# 01-MCU_Core.net
KiCad netlist of a schematic drawn in Altium Designer
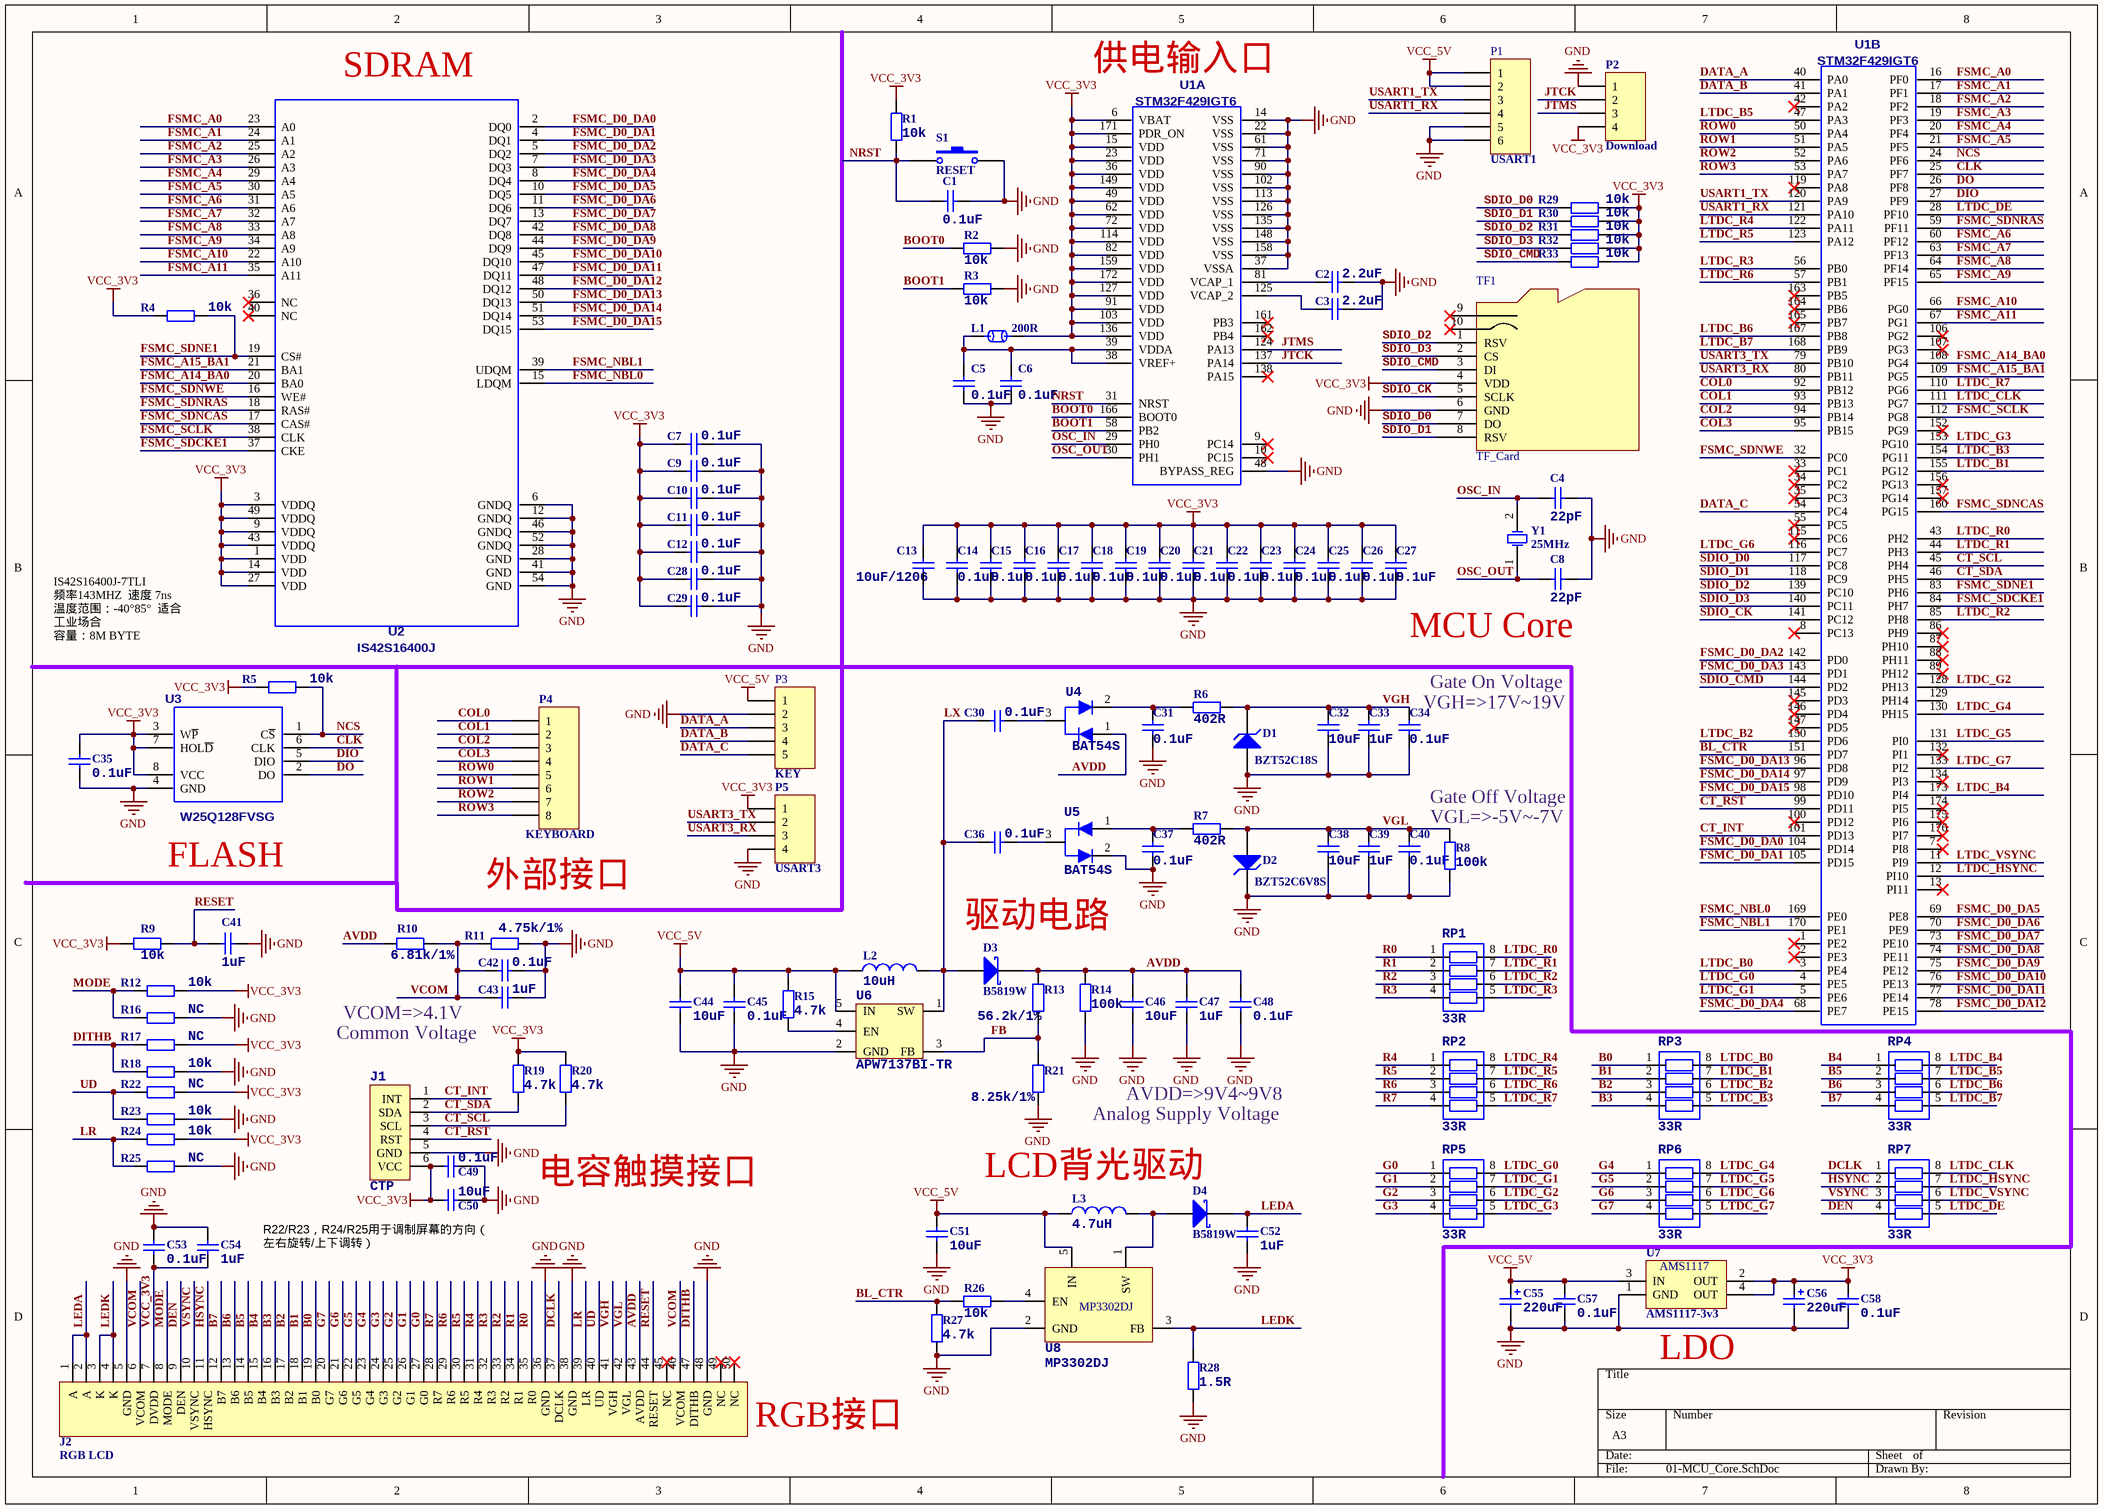
[diagram p0: 01-MCU_Core.SchDoc]

(export (version "E")
  (design (tool "Eeschema 10.0.6"))
  (components
    (comp (ref "C1")
      (value "0.1uF")
      (footprint "C0603")
      (description "CAP CER 10000PF 100V X7R 0603")
      (fields
        (field (name "MANUFACTURER") "TDK Corporation")
        (field (name "MANUFACTURER PART NUMBER") "C1608X7R2A103K080AA")
      )
      (libsource (lib "Desiger_Schlib") (part "Cap1"))
    )
    (comp (ref "C2")
      (value "2.2uF")
      (footprint "C0603")
      (description "CAP CER 10000PF 100V X7R 0603")
      (fields
        (field (name "MANUFACTURER") "TDK Corporation")
        (field (name "MANUFACTURER PART NUMBER") "C1608X7R2A103K080AA")
      )
      (libsource (lib "Desiger_Schlib") (part "Cap1"))
    )
    (comp (ref "C3")
      (value "2.2uF")
      (footprint "C0603")
      (description "CAP CER 10000PF 100V X7R 0603")
      (fields
        (field (name "MANUFACTURER") "TDK Corporation")
        (field (name "MANUFACTURER PART NUMBER") "C1608X7R2A103K080AA")
      )
      (libsource (lib "Desiger_Schlib") (part "Cap1"))
    )
    (comp (ref "C4")
      (value "22pF")
      (footprint "C0603")
      (description "CAP CER 10000PF 100V X7R 0603")
      (fields
        (field (name "MANUFACTURER") "TDK Corporation")
        (field (name "MANUFACTURER PART NUMBER") "C1608X7R2A103K080AA")
      )
      (libsource (lib "Desiger_Schlib") (part "Cap1"))
    )
    (comp (ref "C5")
      (value "0.1uF")
      (footprint "C0603")
      (description "CAP CER 10000PF 100V X7R 0603")
      (fields
        (field (name "MANUFACTURER") "TDK Corporation")
        (field (name "MANUFACTURER PART NUMBER") "C1608X7R2A103K080AA")
      )
      (libsource (lib "Desiger_Schlib") (part "Cap1"))
    )
    (comp (ref "C6")
      (value "0.1uF")
      (footprint "C0603")
      (description "CAP CER 10000PF 100V X7R 0603")
      (fields
        (field (name "MANUFACTURER") "TDK Corporation")
        (field (name "MANUFACTURER PART NUMBER") "C1608X7R2A103K080AA")
      )
      (libsource (lib "Desiger_Schlib") (part "Cap1"))
    )
    (comp (ref "C7")
      (value "0.1uF")
      (footprint "C0603")
      (description "CAP CER 10000PF 100V X7R 0603")
      (fields
        (field (name "MANUFACTURER") "TDK Corporation")
        (field (name "MANUFACTURER PART NUMBER") "C1608X7R2A103K080AA")
      )
      (libsource (lib "Desiger_Schlib") (part "Cap1"))
    )
    (comp (ref "C8")
      (value "22pF")
      (footprint "C0603")
      (description "CAP CER 10000PF 100V X7R 0603")
      (fields
        (field (name "MANUFACTURER") "TDK Corporation")
        (field (name "MANUFACTURER PART NUMBER") "C1608X7R2A103K080AA")
      )
      (libsource (lib "Desiger_Schlib") (part "Cap1"))
    )
    (comp (ref "C9")
      (value "0.1uF")
      (footprint "C0603")
      (description "CAP CER 10000PF 100V X7R 0603")
      (fields
        (field (name "MANUFACTURER") "TDK Corporation")
        (field (name "MANUFACTURER PART NUMBER") "C1608X7R2A103K080AA")
      )
      (libsource (lib "Desiger_Schlib") (part "Cap1"))
    )
    (comp (ref "C10")
      (value "0.1uF")
      (footprint "C0603")
      (description "CAP CER 10000PF 100V X7R 0603")
      (fields
        (field (name "MANUFACTURER") "TDK Corporation")
        (field (name "MANUFACTURER PART NUMBER") "C1608X7R2A103K080AA")
      )
      (libsource (lib "Desiger_Schlib") (part "Cap1"))
    )
    (comp (ref "C11")
      (value "0.1uF")
      (footprint "C0603")
      (description "CAP CER 10000PF 100V X7R 0603")
      (fields
        (field (name "MANUFACTURER") "TDK Corporation")
        (field (name "MANUFACTURER PART NUMBER") "C1608X7R2A103K080AA")
      )
      (libsource (lib "Desiger_Schlib") (part "Cap1"))
    )
    (comp (ref "C12")
      (value "0.1uF")
      (footprint "C0603")
      (description "CAP CER 10000PF 100V X7R 0603")
      (fields
        (field (name "MANUFACTURER") "TDK Corporation")
        (field (name "MANUFACTURER PART NUMBER") "C1608X7R2A103K080AA")
      )
      (libsource (lib "Desiger_Schlib") (part "Cap1"))
    )
    (comp (ref "C13")
      (value "10uF/1206")
      (footprint "C1206")
      (description "CAP CER 10000PF 100V X7R 0603")
      (fields
        (field (name "MANUFACTURER") "TDK Corporation")
        (field (name "MANUFACTURER PART NUMBER") "C1608X7R2A103K080AA")
      )
      (libsource (lib "Desiger_Schlib") (part "Cap1"))
    )
    (comp (ref "C14")
      (value "0.1uF")
      (footprint "C0603")
      (description "CAP CER 10000PF 100V X7R 0603")
      (fields
        (field (name "MANUFACTURER") "TDK Corporation")
        (field (name "MANUFACTURER PART NUMBER") "C1608X7R2A103K080AA")
      )
      (libsource (lib "Desiger_Schlib") (part "Cap1"))
    )
    (comp (ref "C15")
      (value "0.1uF")
      (footprint "C0603")
      (description "CAP CER 10000PF 100V X7R 0603")
      (fields
        (field (name "MANUFACTURER") "TDK Corporation")
        (field (name "MANUFACTURER PART NUMBER") "C1608X7R2A103K080AA")
      )
      (libsource (lib "Desiger_Schlib") (part "Cap1"))
    )
    (comp (ref "C16")
      (value "0.1uF")
      (footprint "C0603")
      (description "CAP CER 10000PF 100V X7R 0603")
      (fields
        (field (name "MANUFACTURER") "TDK Corporation")
        (field (name "MANUFACTURER PART NUMBER") "C1608X7R2A103K080AA")
      )
      (libsource (lib "Desiger_Schlib") (part "Cap1"))
    )
    (comp (ref "C17")
      (value "0.1uF")
      (footprint "C0603")
      (description "CAP CER 10000PF 100V X7R 0603")
      (fields
        (field (name "MANUFACTURER") "TDK Corporation")
        (field (name "MANUFACTURER PART NUMBER") "C1608X7R2A103K080AA")
      )
      (libsource (lib "Desiger_Schlib") (part "Cap1"))
    )
    (comp (ref "C18")
      (value "0.1uF")
      (footprint "C0603")
      (description "CAP CER 10000PF 100V X7R 0603")
      (fields
        (field (name "MANUFACTURER") "TDK Corporation")
        (field (name "MANUFACTURER PART NUMBER") "C1608X7R2A103K080AA")
      )
      (libsource (lib "Desiger_Schlib") (part "Cap1"))
    )
    (comp (ref "C19")
      (value "0.1uF")
      (footprint "C0603")
      (description "CAP CER 10000PF 100V X7R 0603")
      (fields
        (field (name "MANUFACTURER") "TDK Corporation")
        (field (name "MANUFACTURER PART NUMBER") "C1608X7R2A103K080AA")
      )
      (libsource (lib "Desiger_Schlib") (part "Cap1"))
    )
    (comp (ref "C20")
      (value "0.1uF")
      (footprint "C0603")
      (description "CAP CER 10000PF 100V X7R 0603")
      (fields
        (field (name "MANUFACTURER") "TDK Corporation")
        (field (name "MANUFACTURER PART NUMBER") "C1608X7R2A103K080AA")
      )
      (libsource (lib "Desiger_Schlib") (part "Cap1"))
    )
    (comp (ref "C21")
      (value "0.1uF")
      (footprint "C0603")
      (description "CAP CER 10000PF 100V X7R 0603")
      (fields
        (field (name "MANUFACTURER") "TDK Corporation")
        (field (name "MANUFACTURER PART NUMBER") "C1608X7R2A103K080AA")
      )
      (libsource (lib "Desiger_Schlib") (part "Cap1"))
    )
    (comp (ref "C22")
      (value "0.1uF")
      (footprint "C0603")
      (description "CAP CER 10000PF 100V X7R 0603")
      (fields
        (field (name "MANUFACTURER") "TDK Corporation")
        (field (name "MANUFACTURER PART NUMBER") "C1608X7R2A103K080AA")
      )
      (libsource (lib "Desiger_Schlib") (part "Cap1"))
    )
    (comp (ref "C23")
      (value "0.1uF")
      (footprint "C0603")
      (description "CAP CER 10000PF 100V X7R 0603")
      (fields
        (field (name "MANUFACTURER") "TDK Corporation")
        (field (name "MANUFACTURER PART NUMBER") "C1608X7R2A103K080AA")
      )
      (libsource (lib "Desiger_Schlib") (part "Cap1"))
    )
    (comp (ref "C24")
      (value "0.1uF")
      (footprint "C0603")
      (description "CAP CER 10000PF 100V X7R 0603")
      (fields
        (field (name "MANUFACTURER") "TDK Corporation")
        (field (name "MANUFACTURER PART NUMBER") "C1608X7R2A103K080AA")
      )
      (libsource (lib "Desiger_Schlib") (part "Cap1"))
    )
    (comp (ref "C25")
      (value "0.1uF")
      (footprint "C0603")
      (description "CAP CER 10000PF 100V X7R 0603")
      (fields
        (field (name "MANUFACTURER") "TDK Corporation")
        (field (name "MANUFACTURER PART NUMBER") "C1608X7R2A103K080AA")
      )
      (libsource (lib "Desiger_Schlib") (part "Cap1"))
    )
    (comp (ref "C26")
      (value "0.1uF")
      (footprint "C0603")
      (description "CAP CER 10000PF 100V X7R 0603")
      (fields
        (field (name "MANUFACTURER") "TDK Corporation")
        (field (name "MANUFACTURER PART NUMBER") "C1608X7R2A103K080AA")
      )
      (libsource (lib "Desiger_Schlib") (part "Cap1"))
    )
    (comp (ref "C27")
      (value "0.1uF")
      (footprint "C0603")
      (description "CAP CER 10000PF 100V X7R 0603")
      (fields
        (field (name "MANUFACTURER") "TDK Corporation")
        (field (name "MANUFACTURER PART NUMBER") "C1608X7R2A103K080AA")
      )
      (libsource (lib "Desiger_Schlib") (part "Cap1"))
    )
    (comp (ref "C28")
      (value "0.1uF")
      (footprint "C0603")
      (description "CAP CER 10000PF 100V X7R 0603")
      (fields
        (field (name "MANUFACTURER") "TDK Corporation")
        (field (name "MANUFACTURER PART NUMBER") "C1608X7R2A103K080AA")
      )
      (libsource (lib "Desiger_Schlib") (part "Cap1"))
    )
    (comp (ref "C29")
      (value "0.1uF")
      (footprint "C0603")
      (description "CAP CER 10000PF 100V X7R 0603")
      (fields
        (field (name "MANUFACTURER") "TDK Corporation")
        (field (name "MANUFACTURER PART NUMBER") "C1608X7R2A103K080AA")
      )
      (libsource (lib "Desiger_Schlib") (part "Cap1"))
    )
    (comp (ref "C30")
      (value "0.1uF")
      (footprint "C0603")
      (description "CAP CER 10000PF 100V X7R 0603")
      (fields
        (field (name "MANUFACTURER") "TDK Corporation")
        (field (name "MANUFACTURER PART NUMBER") "C1608X7R2A103K080AA")
      )
      (libsource (lib "Desiger_Schlib") (part "Cap1"))
    )
    (comp (ref "C31")
      (value "0.1uF")
      (footprint "C0603")
      (description "CAP CER 10000PF 100V X7R 0603")
      (fields
        (field (name "MANUFACTURER") "TDK Corporation")
        (field (name "MANUFACTURER PART NUMBER") "C1608X7R2A103K080AA")
      )
      (libsource (lib "Desiger_Schlib") (part "Cap1"))
    )
    (comp (ref "C32")
      (value "10uF")
      (footprint "C1206")
      (description "CAP CER 10000PF 100V X7R 0603")
      (fields
        (field (name "MANUFACTURER") "TDK Corporation")
        (field (name "MANUFACTURER PART NUMBER") "C1608X7R2A103K080AA")
      )
      (libsource (lib "Desiger_Schlib") (part "Cap1"))
    )
    (comp (ref "C33")
      (value "1uF")
      (footprint "C0603")
      (description "CAP CER 10000PF 100V X7R 0603")
      (fields
        (field (name "MANUFACTURER") "TDK Corporation")
        (field (name "MANUFACTURER PART NUMBER") "C1608X7R2A103K080AA")
      )
      (libsource (lib "Desiger_Schlib") (part "Cap1"))
    )
    (comp (ref "C34")
      (value "0.1uF")
      (footprint "C0603")
      (description "CAP CER 10000PF 100V X7R 0603")
      (fields
        (field (name "MANUFACTURER") "TDK Corporation")
        (field (name "MANUFACTURER PART NUMBER") "C1608X7R2A103K080AA")
      )
      (libsource (lib "Desiger_Schlib") (part "Cap1"))
    )
    (comp (ref "C35")
      (value "0.1uF")
      (footprint "C0603")
      (description "CAP CER 10000PF 100V X7R 0603")
      (fields
        (field (name "MANUFACTURER") "TDK Corporation")
        (field (name "MANUFACTURER PART NUMBER") "C1608X7R2A103K080AA")
      )
      (libsource (lib "Desiger_Schlib") (part "Cap1"))
    )
    (comp (ref "C36")
      (value "0.1uF")
      (footprint "C0603")
      (description "CAP CER 10000PF 100V X7R 0603")
      (fields
        (field (name "MANUFACTURER") "TDK Corporation")
        (field (name "MANUFACTURER PART NUMBER") "C1608X7R2A103K080AA")
      )
      (libsource (lib "Desiger_Schlib") (part "Cap1"))
    )
    (comp (ref "C37")
      (value "0.1uF")
      (footprint "C0603")
      (description "CAP CER 10000PF 100V X7R 0603")
      (fields
        (field (name "MANUFACTURER") "TDK Corporation")
        (field (name "MANUFACTURER PART NUMBER") "C1608X7R2A103K080AA")
      )
      (libsource (lib "Desiger_Schlib") (part "Cap1"))
    )
    (comp (ref "C38")
      (value "10uF")
      (footprint "C1206")
      (description "CAP CER 10000PF 100V X7R 0603")
      (fields
        (field (name "MANUFACTURER") "TDK Corporation")
        (field (name "MANUFACTURER PART NUMBER") "C1608X7R2A103K080AA")
      )
      (libsource (lib "Desiger_Schlib") (part "Cap1"))
    )
    (comp (ref "C39")
      (value "1uF")
      (footprint "C0603")
      (description "CAP CER 10000PF 100V X7R 0603")
      (fields
        (field (name "MANUFACTURER") "TDK Corporation")
        (field (name "MANUFACTURER PART NUMBER") "C1608X7R2A103K080AA")
      )
      (libsource (lib "Desiger_Schlib") (part "Cap1"))
    )
    (comp (ref "C40")
      (value "0.1uF")
      (footprint "C0603")
      (description "CAP CER 10000PF 100V X7R 0603")
      (fields
        (field (name "MANUFACTURER") "TDK Corporation")
        (field (name "MANUFACTURER PART NUMBER") "C1608X7R2A103K080AA")
      )
      (libsource (lib "Desiger_Schlib") (part "Cap1"))
    )
    (comp (ref "C41")
      (value "1uF")
      (footprint "C0603")
      (description "CAP CER 10000PF 100V X7R 0603")
      (fields
        (field (name "MANUFACTURER") "TDK Corporation")
        (field (name "MANUFACTURER PART NUMBER") "C1608X7R2A103K080AA")
      )
      (libsource (lib "Desiger_Schlib") (part "Cap1"))
    )
    (comp (ref "C42")
      (value "0.1uF")
      (footprint "C0603")
      (description "CAP CER 10000PF 100V X7R 0603")
      (fields
        (field (name "MANUFACTURER") "TDK Corporation")
        (field (name "MANUFACTURER PART NUMBER") "C1608X7R2A103K080AA")
      )
      (libsource (lib "Desiger_Schlib") (part "Cap1"))
    )
    (comp (ref "C43")
      (value "1uF")
      (footprint "C0603")
      (description "CAP CER 10000PF 100V X7R 0603")
      (fields
        (field (name "MANUFACTURER") "TDK Corporation")
        (field (name "MANUFACTURER PART NUMBER") "C1608X7R2A103K080AA")
      )
      (libsource (lib "Desiger_Schlib") (part "Cap1"))
    )
    (comp (ref "C44")
      (value "10uF")
      (footprint "C1206")
      (description "CAP CER 10000PF 100V X7R 0603")
      (fields
        (field (name "MANUFACTURER") "TDK Corporation")
        (field (name "MANUFACTURER PART NUMBER") "C1608X7R2A103K080AA")
      )
      (libsource (lib "Desiger_Schlib") (part "Cap1"))
    )
    (comp (ref "C45")
      (value "0.1uF")
      (footprint "C0603")
      (description "CAP CER 10000PF 100V X7R 0603")
      (fields
        (field (name "MANUFACTURER") "TDK Corporation")
        (field (name "MANUFACTURER PART NUMBER") "C1608X7R2A103K080AA")
      )
      (libsource (lib "Desiger_Schlib") (part "Cap1"))
    )
    (comp (ref "C46")
      (value "10uF")
      (footprint "C1206")
      (description "CAP CER 10000PF 100V X7R 0603")
      (fields
        (field (name "MANUFACTURER") "TDK Corporation")
        (field (name "MANUFACTURER PART NUMBER") "C1608X7R2A103K080AA")
      )
      (libsource (lib "Desiger_Schlib") (part "Cap1"))
    )
    (comp (ref "C47")
      (value "1uF")
      (footprint "C0603")
      (description "CAP CER 10000PF 100V X7R 0603")
      (fields
        (field (name "MANUFACTURER") "TDK Corporation")
        (field (name "MANUFACTURER PART NUMBER") "C1608X7R2A103K080AA")
      )
      (libsource (lib "Desiger_Schlib") (part "Cap1"))
    )
    (comp (ref "C48")
      (value "0.1uF")
      (footprint "C0603")
      (description "CAP CER 10000PF 100V X7R 0603")
      (fields
        (field (name "MANUFACTURER") "TDK Corporation")
        (field (name "MANUFACTURER PART NUMBER") "C1608X7R2A103K080AA")
      )
      (libsource (lib "Desiger_Schlib") (part "Cap1"))
    )
    (comp (ref "C49")
      (value "0.1uF")
      (footprint "C0603")
      (description "CAP CER 10000PF 100V X7R 0603")
      (fields
        (field (name "MANUFACTURER") "TDK Corporation")
        (field (name "MANUFACTURER PART NUMBER") "C1608X7R2A103K080AA")
      )
      (libsource (lib "Desiger_Schlib") (part "Cap1"))
    )
    (comp (ref "C50")
      (value "10uF")
      (footprint "C1206")
      (description "CAP CER 10000PF 100V X7R 0603")
      (fields
        (field (name "MANUFACTURER") "TDK Corporation")
        (field (name "MANUFACTURER PART NUMBER") "C1608X7R2A103K080AA")
      )
      (libsource (lib "Desiger_Schlib") (part "Cap1"))
    )
    (comp (ref "C51")
      (value "10uF")
      (footprint "C1206")
      (description "CAP CER 10000PF 100V X7R 0603")
      (fields
        (field (name "MANUFACTURER") "TDK Corporation")
        (field (name "MANUFACTURER PART NUMBER") "C1608X7R2A103K080AA")
      )
      (libsource (lib "Desiger_Schlib") (part "Cap1"))
    )
    (comp (ref "C52")
      (value "1uF")
      (footprint "C0603")
      (description "CAP CER 10000PF 100V X7R 0603")
      (fields
        (field (name "MANUFACTURER") "TDK Corporation")
        (field (name "MANUFACTURER PART NUMBER") "C1608X7R2A103K080AA")
      )
      (libsource (lib "Desiger_Schlib") (part "Cap1"))
    )
    (comp (ref "C53")
      (value "0.1uF")
      (footprint "C0603")
      (description "CAP CER 10000PF 100V X7R 0603")
      (fields
        (field (name "MANUFACTURER") "TDK Corporation")
        (field (name "MANUFACTURER PART NUMBER") "C1608X7R2A103K080AA")
      )
      (libsource (lib "Desiger_Schlib") (part "Cap1"))
    )
    (comp (ref "C54")
      (value "1uF")
      (footprint "C0603")
      (description "CAP CER 10000PF 100V X7R 0603")
      (fields
        (field (name "MANUFACTURER") "TDK Corporation")
        (field (name "MANUFACTURER PART NUMBER") "C1608X7R2A103K080AA")
      )
      (libsource (lib "Desiger_Schlib") (part "Cap1"))
    )
    (comp (ref "C55")
      (value "220uF")
      (footprint "Desiger_Pcblib:C_SMD(6.3x5.3)")
      (description "CAP TANT 10UF 10V 10% 1206")
      (fields
        (field (name "MANUFACTURER") "KEMET")
        (field (name "MANUFACTURER PART NUMBER") "T491A106K010AT7280")
      )
      (libsource (lib "Desiger_Schlib") (part "Cap2"))
    )
    (comp (ref "C56")
      (value "220uF")
      (footprint "Desiger_Pcblib:C_SMD(6.3x5.3)")
      (description "CAP TANT 10UF 10V 10% 1206")
      (fields
        (field (name "MANUFACTURER") "KEMET")
        (field (name "MANUFACTURER PART NUMBER") "T491A106K010AT7280")
      )
      (libsource (lib "Desiger_Schlib") (part "Cap2"))
    )
    (comp (ref "C57")
      (value "0.1uF")
      (footprint "C0603")
      (description "CAP CER 10000PF 100V X7R 0603")
      (fields
        (field (name "MANUFACTURER") "TDK Corporation")
        (field (name "MANUFACTURER PART NUMBER") "C1608X7R2A103K080AA")
      )
      (libsource (lib "Desiger_Schlib") (part "Cap1"))
    )
    (comp (ref "C58")
      (value "0.1uF")
      (footprint "C0603")
      (description "CAP CER 10000PF 100V X7R 0603")
      (fields
        (field (name "MANUFACTURER") "TDK Corporation")
        (field (name "MANUFACTURER PART NUMBER") "C1608X7R2A103K080AA")
      )
      (libsource (lib "Desiger_Schlib") (part "Cap1"))
    )
    (comp (ref "D1")
      (value "BZT52C18S")
      (footprint "Desiger_Pcblib:SOD323")
      (description "Zener Diode")
      (fields (field (name "PUBLISHER") "Altium Limited"))
      (libsource (lib "Miscellaneous Devices") (part "D Zener"))
    )
    (comp (ref "D2")
      (value "BZT52C6V8S")
      (footprint "Desiger_Pcblib:SOD323")
      (description "Zener Diode")
      (fields (field (name "PUBLISHER") "Altium Limited"))
      (libsource (lib "Miscellaneous Devices") (part "D Zener"))
    )
    (comp (ref "D3")
      (value "B5819W")
      (footprint "SOD123")
      (description "Schottky Diode")
      (fields (field (name "PUBLISHER") "Altium Limited"))
      (libsource (lib "Miscellaneous Devices") (part "D Schottky"))
    )
    (comp (ref "D4")
      (value "B5819W")
      (footprint "SOD123")
      (description "Schottky Diode")
      (fields (field (name "PUBLISHER") "Altium Limited"))
      (libsource (lib "Miscellaneous Devices") (part "D Schottky"))
    )
    (comp (ref "J1") (value "CTP") (footprint "CTOUCH_6_TOP") (libsource (lib "Desiger_Schlib") (part "CTP")))
    (comp (ref "J2")
      (value "RGB LCD")
      (footprint "FPC-TOP50")
      (libsource (lib "Desiger_Schlib") (part "LCD_RGB_7R"))
    )
    (comp (ref "L1")
      (value "200R")
      (footprint "L0603")
      (description "FERRITE BEAD 1 KOHM 0603 1LN")
      (fields
        (field (name "MANUFACTURER") "Taiyo Yuden")
        (field (name "MANUFACTURER PART NUMBER") "FBMH1608HM102-T")
      )
      (libsource (lib "Desiger_Schlib") (part "FBMH1608HM102-T"))
    )
    (comp (ref "L2")
      (value "10uH")
      (footprint "ind2sm-4x4x3")
      (description "FIXED IND 240NH 4.4A 22MOHM SMD")
      (fields
        (field (name "MANUFACTURER") "Samsung Electro-Mechanics")
        (field (name "MANUFACTURER PART NUMBER") "CIGT201210UHR24MNE")
      )
      (libsource (lib "Desiger_Schlib") (part "Inductors"))
    )
    (comp (ref "L3")
      (value "4.7uH")
      (footprint "ind2sm-4x4x3")
      (description "FIXED IND 240NH 4.4A 22MOHM SMD")
      (fields
        (field (name "MANUFACTURER") "Samsung Electro-Mechanics")
        (field (name "MANUFACTURER PART NUMBER") "CIGT201210UHR24MNE")
      )
      (libsource (lib "Desiger_Schlib") (part "Inductors"))
    )
    (comp (ref "P1")
      (value "USART1")
      (footprint "Desiger_Pcblib:XH2.54-6P")
      (description "Header, 6-Pin")
      (fields (field (name "PUBLISHER") "Altium Limited"))
      (libsource (lib "Miscellaneous Connectors") (part "Header 6"))
    )
    (comp (ref "P2")
      (value "Download")
      (footprint "Desiger_Pcblib:1.25PWT-4P")
      (description "Header, 4-Pin")
      (fields (field (name "PUBLISHER") "Altium Limited"))
      (libsource (lib "Miscellaneous Connectors") (part "Header 4"))
    )
    (comp (ref "P3")
      (value "KEY")
      (footprint "Desiger_Pcblib:XH2.54-5P")
      (description "Header, 5-Pin")
      (fields (field (name "PUBLISHER") "Altium Limited"))
      (libsource (lib "Miscellaneous Connectors") (part "Header 5"))
    )
    (comp (ref "P4")
      (value "KEYBOARD")
      (footprint "Desiger_Pcblib:XH2.54-8P")
      (description "Header, 8-Pin")
      (fields (field (name "PUBLISHER") "Altium Limited"))
      (libsource (lib "Miscellaneous Connectors") (part "Header 8"))
    )
    (comp (ref "P5")
      (value "USART3")
      (footprint "Desiger_Pcblib:XH2.54-4P")
      (description "Header, 4-Pin")
      (fields (field (name "PUBLISHER") "Altium Limited"))
      (libsource (lib "Miscellaneous Connectors") (part "Header 4"))
    )
    (comp (ref "R1")
      (value "10k")
      (footprint "R0603")
      (description "RES SMD 5.1K OHM 5% 1/10W 0603")
      (fields
        (field (name "MANUFACTURER") "Bourns Inc.")
        (field (name "MANUFACTURER PART NUMBER") "CR0603-JW-512ELF")
      )
      (libsource (lib "") (part "Res2_2"))
    )
    (comp (ref "R2")
      (value "10k")
      (footprint "R0603")
      (description "RES SMD 5.1K OHM 5% 1/10W 0603")
      (fields
        (field (name "MANUFACTURER") "Bourns Inc.")
        (field (name "MANUFACTURER PART NUMBER") "CR0603-JW-512ELF")
      )
      (libsource (lib "Desiger_Schlib") (part "Res2"))
    )
    (comp (ref "R3")
      (value "10k")
      (footprint "R0603")
      (description "RES SMD 5.1K OHM 5% 1/10W 0603")
      (fields
        (field (name "MANUFACTURER") "Bourns Inc.")
        (field (name "MANUFACTURER PART NUMBER") "CR0603-JW-512ELF")
      )
      (libsource (lib "Desiger_Schlib") (part "Res2"))
    )
    (comp (ref "R4")
      (value "10k")
      (footprint "R0603")
      (description "RES SMD 5.1K OHM 5% 1/10W 0603")
      (fields
        (field (name "MANUFACTURER") "Bourns Inc.")
        (field (name "MANUFACTURER PART NUMBER") "CR0603-JW-512ELF")
      )
      (libsource (lib "Desiger_Schlib") (part "Res2"))
    )
    (comp (ref "R5")
      (value "10k")
      (footprint "R0603")
      (description "RES SMD 5.1K OHM 5% 1/10W 0603")
      (fields
        (field (name "MANUFACTURER") "Bourns Inc.")
        (field (name "MANUFACTURER PART NUMBER") "CR0603-JW-512ELF")
      )
      (libsource (lib "Desiger_Schlib") (part "Res2"))
    )
    (comp (ref "R6")
      (value "402R")
      (footprint "R0603")
      (description "RES SMD 5.1K OHM 5% 1/10W 0603")
      (fields
        (field (name "MANUFACTURER") "Bourns Inc.")
        (field (name "MANUFACTURER PART NUMBER") "CR0603-JW-512ELF")
      )
      (libsource (lib "Desiger_Schlib") (part "Res2"))
    )
    (comp (ref "R7")
      (value "402R")
      (footprint "R0603")
      (description "RES SMD 5.1K OHM 5% 1/10W 0603")
      (fields
        (field (name "MANUFACTURER") "Bourns Inc.")
        (field (name "MANUFACTURER PART NUMBER") "CR0603-JW-512ELF")
      )
      (libsource (lib "Desiger_Schlib") (part "Res2"))
    )
    (comp (ref "R8")
      (value "100k")
      (footprint "R0603")
      (description "RES SMD 5.1K OHM 5% 1/10W 0603")
      (fields
        (field (name "MANUFACTURER") "Bourns Inc.")
        (field (name "MANUFACTURER PART NUMBER") "CR0603-JW-512ELF")
      )
      (libsource (lib "") (part "Res2_2"))
    )
    (comp (ref "R9")
      (value "10k")
      (footprint "R0603")
      (description "RES SMD 5.1K OHM 5% 1/10W 0603")
      (fields
        (field (name "MANUFACTURER") "Bourns Inc.")
        (field (name "MANUFACTURER PART NUMBER") "CR0603-JW-512ELF")
      )
      (libsource (lib "Desiger_Schlib") (part "Res2"))
    )
    (comp (ref "R10")
      (value "6.81k/1%")
      (footprint "R0603")
      (description "RES SMD 5.1K OHM 5% 1/10W 0603")
      (fields
        (field (name "MANUFACTURER") "Bourns Inc.")
        (field (name "MANUFACTURER PART NUMBER") "CR0603-JW-512ELF")
      )
      (libsource (lib "Desiger_Schlib") (part "Res2"))
    )
    (comp (ref "R11")
      (value "4.75k/1%")
      (footprint "R0603")
      (description "RES SMD 5.1K OHM 5% 1/10W 0603")
      (fields
        (field (name "MANUFACTURER") "Bourns Inc.")
        (field (name "MANUFACTURER PART NUMBER") "CR0603-JW-512ELF")
      )
      (libsource (lib "Desiger_Schlib") (part "Res2"))
    )
    (comp (ref "R12")
      (value "10k")
      (footprint "R0603")
      (description "RES SMD 5.1K OHM 5% 1/10W 0603")
      (fields
        (field (name "MANUFACTURER") "Bourns Inc.")
        (field (name "MANUFACTURER PART NUMBER") "CR0603-JW-512ELF")
      )
      (libsource (lib "Desiger_Schlib") (part "Res2"))
    )
    (comp (ref "R13")
      (value "56.2k/1%")
      (footprint "R0603")
      (description "RES SMD 5.1K OHM 5% 1/10W 0603")
      (fields
        (field (name "MANUFACTURER") "Bourns Inc.")
        (field (name "MANUFACTURER PART NUMBER") "CR0603-JW-512ELF")
      )
      (libsource (lib "") (part "Res2_2"))
    )
    (comp (ref "R14")
      (value "100k")
      (footprint "R0603")
      (description "RES SMD 5.1K OHM 5% 1/10W 0603")
      (fields
        (field (name "MANUFACTURER") "Bourns Inc.")
        (field (name "MANUFACTURER PART NUMBER") "CR0603-JW-512ELF")
      )
      (libsource (lib "") (part "Res2_2"))
    )
    (comp (ref "R15")
      (value "4.7k")
      (footprint "R0603")
      (description "RES SMD 5.1K OHM 5% 1/10W 0603")
      (fields
        (field (name "MANUFACTURER") "Bourns Inc.")
        (field (name "MANUFACTURER PART NUMBER") "CR0603-JW-512ELF")
      )
      (libsource (lib "") (part "Res2_2"))
    )
    (comp (ref "R16")
      (value "NC")
      (footprint "R0603")
      (description "RES SMD 5.1K OHM 5% 1/10W 0603")
      (fields
        (field (name "MANUFACTURER") "Bourns Inc.")
        (field (name "MANUFACTURER PART NUMBER") "CR0603-JW-512ELF")
      )
      (libsource (lib "Desiger_Schlib") (part "Res2"))
    )
    (comp (ref "R17")
      (value "NC")
      (footprint "R0603")
      (description "RES SMD 5.1K OHM 5% 1/10W 0603")
      (fields
        (field (name "MANUFACTURER") "Bourns Inc.")
        (field (name "MANUFACTURER PART NUMBER") "CR0603-JW-512ELF")
      )
      (libsource (lib "Desiger_Schlib") (part "Res2"))
    )
    (comp (ref "R18")
      (value "10k")
      (footprint "R0603")
      (description "RES SMD 5.1K OHM 5% 1/10W 0603")
      (fields
        (field (name "MANUFACTURER") "Bourns Inc.")
        (field (name "MANUFACTURER PART NUMBER") "CR0603-JW-512ELF")
      )
      (libsource (lib "Desiger_Schlib") (part "Res2"))
    )
    (comp (ref "R19")
      (value "4.7k")
      (footprint "R0603")
      (description "RES SMD 5.1K OHM 5% 1/10W 0603")
      (fields
        (field (name "MANUFACTURER") "Bourns Inc.")
        (field (name "MANUFACTURER PART NUMBER") "CR0603-JW-512ELF")
      )
      (libsource (lib "") (part "Res2_2"))
    )
    (comp (ref "R20")
      (value "4.7k")
      (footprint "R0603")
      (description "RES SMD 5.1K OHM 5% 1/10W 0603")
      (fields
        (field (name "MANUFACTURER") "Bourns Inc.")
        (field (name "MANUFACTURER PART NUMBER") "CR0603-JW-512ELF")
      )
      (libsource (lib "") (part "Res2_2"))
    )
    (comp (ref "R21")
      (value "8.25k/1%")
      (footprint "R0603")
      (description "RES SMD 5.1K OHM 5% 1/10W 0603")
      (fields
        (field (name "MANUFACTURER") "Bourns Inc.")
        (field (name "MANUFACTURER PART NUMBER") "CR0603-JW-512ELF")
      )
      (libsource (lib "") (part "Res2_2"))
    )
    (comp (ref "R22")
      (value "NC")
      (footprint "R0603")
      (description "RES SMD 5.1K OHM 5% 1/10W 0603")
      (fields
        (field (name "MANUFACTURER") "Bourns Inc.")
        (field (name "MANUFACTURER PART NUMBER") "CR0603-JW-512ELF")
      )
      (libsource (lib "Desiger_Schlib") (part "Res2"))
    )
    (comp (ref "R23")
      (value "10k")
      (footprint "R0603")
      (description "RES SMD 5.1K OHM 5% 1/10W 0603")
      (fields
        (field (name "MANUFACTURER") "Bourns Inc.")
        (field (name "MANUFACTURER PART NUMBER") "CR0603-JW-512ELF")
      )
      (libsource (lib "Desiger_Schlib") (part "Res2"))
    )
    (comp (ref "R24")
      (value "10k")
      (footprint "R0603")
      (description "RES SMD 5.1K OHM 5% 1/10W 0603")
      (fields
        (field (name "MANUFACTURER") "Bourns Inc.")
        (field (name "MANUFACTURER PART NUMBER") "CR0603-JW-512ELF")
      )
      (libsource (lib "Desiger_Schlib") (part "Res2"))
    )
    (comp (ref "R25")
      (value "NC")
      (footprint "R0603")
      (description "RES SMD 5.1K OHM 5% 1/10W 0603")
      (fields
        (field (name "MANUFACTURER") "Bourns Inc.")
        (field (name "MANUFACTURER PART NUMBER") "CR0603-JW-512ELF")
      )
      (libsource (lib "Desiger_Schlib") (part "Res2"))
    )
    (comp (ref "R26")
      (value "10k")
      (footprint "R0603")
      (description "RES SMD 5.1K OHM 5% 1/10W 0603")
      (fields
        (field (name "MANUFACTURER") "Bourns Inc.")
        (field (name "MANUFACTURER PART NUMBER") "CR0603-JW-512ELF")
      )
      (libsource (lib "") (part "Res2_1"))
    )
    (comp (ref "R27")
      (value "4.7k")
      (footprint "R0603")
      (description "RES SMD 5.1K OHM 5% 1/10W 0603")
      (fields
        (field (name "MANUFACTURER") "Bourns Inc.")
        (field (name "MANUFACTURER PART NUMBER") "CR0603-JW-512ELF")
      )
      (libsource (lib "") (part "Res2_2"))
    )
    (comp (ref "R28")
      (value "1.5R")
      (footprint "R0603")
      (description "RES SMD 5.1K OHM 5% 1/10W 0603")
      (fields
        (field (name "MANUFACTURER") "Bourns Inc.")
        (field (name "MANUFACTURER PART NUMBER") "CR0603-JW-512ELF")
      )
      (libsource (lib "") (part "Res2_2"))
    )
    (comp (ref "R29")
      (value "10k")
      (footprint "R0603")
      (description "RES SMD 5.1K OHM 5% 1/10W 0603")
      (fields
        (field (name "MANUFACTURER") "Bourns Inc.")
        (field (name "MANUFACTURER PART NUMBER") "CR0603-JW-512ELF")
      )
      (libsource (lib "Desiger_Schlib") (part "Res2"))
    )
    (comp (ref "R30")
      (value "10k")
      (footprint "R0603")
      (description "RES SMD 5.1K OHM 5% 1/10W 0603")
      (fields
        (field (name "MANUFACTURER") "Bourns Inc.")
        (field (name "MANUFACTURER PART NUMBER") "CR0603-JW-512ELF")
      )
      (libsource (lib "Desiger_Schlib") (part "Res2"))
    )
    (comp (ref "R31")
      (value "10k")
      (footprint "R0603")
      (description "RES SMD 5.1K OHM 5% 1/10W 0603")
      (fields
        (field (name "MANUFACTURER") "Bourns Inc.")
        (field (name "MANUFACTURER PART NUMBER") "CR0603-JW-512ELF")
      )
      (libsource (lib "Desiger_Schlib") (part "Res2"))
    )
    (comp (ref "R32")
      (value "10k")
      (footprint "R0603")
      (description "RES SMD 5.1K OHM 5% 1/10W 0603")
      (fields
        (field (name "MANUFACTURER") "Bourns Inc.")
        (field (name "MANUFACTURER PART NUMBER") "CR0603-JW-512ELF")
      )
      (libsource (lib "Desiger_Schlib") (part "Res2"))
    )
    (comp (ref "R33")
      (value "10k")
      (footprint "R0603")
      (description "RES SMD 5.1K OHM 5% 1/10W 0603")
      (fields
        (field (name "MANUFACTURER") "Bourns Inc.")
        (field (name "MANUFACTURER PART NUMBER") "CR0603-JW-512ELF")
      )
      (libsource (lib "Desiger_Schlib") (part "Res2"))
    )
    (comp (ref "RP1")
      (value "33R")
      (footprint "Desiger_Pcblib:RA0603")
      (libsource (lib "Desiger_Schlib") (part "RPX4"))
    )
    (comp (ref "RP2")
      (value "33R")
      (footprint "Desiger_Pcblib:RA0603")
      (libsource (lib "Desiger_Schlib") (part "RPX4"))
    )
    (comp (ref "RP3")
      (value "33R")
      (footprint "Desiger_Pcblib:RA0603")
      (libsource (lib "Desiger_Schlib") (part "RPX4"))
    )
    (comp (ref "RP4")
      (value "33R")
      (footprint "Desiger_Pcblib:RA0603")
      (libsource (lib "Desiger_Schlib") (part "RPX4"))
    )
    (comp (ref "RP5")
      (value "33R")
      (footprint "Desiger_Pcblib:RA0603")
      (libsource (lib "Desiger_Schlib") (part "RPX4"))
    )
    (comp (ref "RP6")
      (value "33R")
      (footprint "Desiger_Pcblib:RA0603")
      (libsource (lib "Desiger_Schlib") (part "RPX4"))
    )
    (comp (ref "RP7")
      (value "33R")
      (footprint "Desiger_Pcblib:RA0603")
      (libsource (lib "Desiger_Schlib") (part "RPX4"))
    )
    (comp (ref "S1")
      (value "RESET")
      (footprint "Desiger_Pcblib:micro button_2_SMD")
      (description "Switch")
      (fields (field (name "PUBLISHER") "Altium Limited"))
      (libsource (lib "Miscellaneous Devices") (part "SW-PB"))
    )
    (comp (ref "TF1") (value "TF_Card") (footprint "SD Card") (libsource (lib "NET&USB") (part "TF_CADE_1")))
    (comp (ref "U1")
      (value "STM32F429IGT6")
      (footprint "Desiger_Pcblib:LQFP24X24_176")
      (libsource (lib "F429_F746_F767_Core") (part "STM32F767IGT6"))
    )
    (comp (ref "U2")
      (value "IS42S16400J")
      (footprint "TSOP-54")
      (libsource (lib "F429_F746_F767_Core") (part "IS42S16400J"))
    )
    (comp (ref "U3")
      (value "W25Q128FVSG")
      (footprint "SOP8-208")
      (libsource (lib "F429_F746_F767_Core") (part "W25Q128FVSG"))
    )
    (comp (ref "U4")
      (value "BAT54S")
      (footprint "SOT_23_3")
      (libsource (lib "Desiger_Schlib") (part "BAT54S"))
    )
    (comp (ref "U5")
      (value "BAT54S")
      (footprint "SOT_23_3")
      (libsource (lib "Desiger_Schlib") (part "BAT54S"))
    )
    (comp (ref "U6")
      (value "APW7137BI-TR")
      (footprint "SOT23-5")
      (libsource (lib "Desiger_Schlib") (part "APW7137BI-TR"))
    )
    (comp (ref "U7")
      (value "AMS1117-3v3")
      (footprint "Desiger_Pcblib:SOT223")
      (libsource (lib "Desiger_Schlib") (part "AMS1117-3v3"))
    )
    (comp (ref "U8")
      (value "MP3302DJ")
      (footprint "SOT23-5")
      (libsource (lib "Desiger_Schlib") (part "MP3302DJ"))
    )
    (comp (ref "Y1")
      (value "25MHz")
      (footprint "Desiger_Pcblib:HC-49SMD")
      (description "Crystal Oscillator")
      (fields (field (name "PUBLISHER") "Altium Limited"))
      (libsource (lib "Miscellaneous Devices") (part "XTAL"))
    )
  )
  (nets
    (net (code "1") (name "/AVDD") (class "Default")
      (node (ref "C46") (pin "2") (pinfunction "2_2") (pintype "passive"))
      (node (ref "C47") (pin "2") (pinfunction "2_2") (pintype "passive"))
      (node (ref "C48") (pin "2") (pinfunction "2_2") (pintype "passive"))
      (node (ref "D3") (pin "2") (pinfunction "K_2") (pintype "passive"))
      (node (ref "J2") (pin "43") (pinfunction "AVDD_43") (pintype "passive"))
      (node (ref "R10") (pin "1") (pinfunction "1_1") (pintype "passive"))
      (node (ref "R13") (pin "2") (pinfunction "2_2") (pintype "passive"))
      (node (ref "R14") (pin "2") (pinfunction "2_2") (pintype "passive"))
      (node (ref "U4") (pin "1") (pinfunction "1_1") (pintype "passive"))
    )
    (net (code "2") (name "/B0") (class "Default")
      (node (ref "J2") (pin "19") (pinfunction "B0_19") (pintype "passive"))
      (node (ref "RP3") (pin "1") (pinfunction "1_1") (pintype "passive"))
    )
    (net (code "3") (name "/B1") (class "Default")
      (node (ref "J2") (pin "18") (pinfunction "B1_18") (pintype "passive"))
      (node (ref "RP3") (pin "2") (pinfunction "2_2") (pintype "passive"))
    )
    (net (code "4") (name "/B2") (class "Default")
      (node (ref "J2") (pin "17") (pinfunction "B2_17") (pintype "passive"))
      (node (ref "RP3") (pin "3") (pinfunction "3_3") (pintype "passive"))
    )
    (net (code "5") (name "/B3") (class "Default")
      (node (ref "J2") (pin "16") (pinfunction "B3_16") (pintype "passive"))
      (node (ref "RP3") (pin "4") (pinfunction "4_4") (pintype "passive"))
    )
    (net (code "6") (name "/B4") (class "Default")
      (node (ref "J2") (pin "15") (pinfunction "B4_15") (pintype "passive"))
      (node (ref "RP4") (pin "1") (pinfunction "1_1") (pintype "passive"))
    )
    (net (code "7") (name "/B5") (class "Default")
      (node (ref "J2") (pin "14") (pinfunction "B5_14") (pintype "passive"))
      (node (ref "RP4") (pin "2") (pinfunction "2_2") (pintype "passive"))
    )
    (net (code "8") (name "/B6") (class "Default")
      (node (ref "J2") (pin "13") (pinfunction "B6_13") (pintype "passive"))
      (node (ref "RP4") (pin "3") (pinfunction "3_3") (pintype "passive"))
    )
    (net (code "9") (name "/B7") (class "Default")
      (node (ref "J2") (pin "12") (pinfunction "B7_12") (pintype "passive"))
      (node (ref "RP4") (pin "4") (pinfunction "4_4") (pintype "passive"))
    )
    (net (code "10") (name "/BL_CTR") (class "Default")
      (node (ref "R26") (pin "2") (pinfunction "2_2") (pintype "passive"))
      (node (ref "R27") (pin "2") (pinfunction "2_2") (pintype "passive"))
      (node (ref "U1") (pin "151") (pinfunction "PD7_151") (pintype "passive"))
    )
    (net (code "11") (name "/BOOT0") (class "Default")
      (node (ref "R2") (pin "1") (pinfunction "1_1") (pintype "passive"))
      (node (ref "U1") (pin "166") (pinfunction "BOOT0_166") (pintype "passive"))
    )
    (net (code "12") (name "/BOOT1") (class "Default")
      (node (ref "R3") (pin "1") (pinfunction "1_1") (pintype "passive"))
      (node (ref "U1") (pin "58") (pinfunction "PB2_58") (pintype "passive"))
    )
    (net (code "13") (name "/CLK") (class "Default")
      (node (ref "U1") (pin "25") (pinfunction "PF7_25") (pintype "passive"))
      (node (ref "U3") (pin "6") (pinfunction "CLK_6") (pintype "passive"))
    )
    (net (code "14") (name "/COL0") (class "Default")
      (node (ref "P4") (pin "1") (pinfunction "1_1") (pintype "passive"))
      (node (ref "U1") (pin "92") (pinfunction "PB12_92") (pintype "passive"))
    )
    (net (code "15") (name "/COL1") (class "Default")
      (node (ref "P4") (pin "2") (pinfunction "2_2") (pintype "passive"))
      (node (ref "U1") (pin "93") (pinfunction "PB13_93") (pintype "passive"))
    )
    (net (code "16") (name "/COL2") (class "Default")
      (node (ref "P4") (pin "3") (pinfunction "3_3") (pintype "passive"))
      (node (ref "U1") (pin "94") (pinfunction "PB14_94") (pintype "passive"))
    )
    (net (code "17") (name "/COL3") (class "Default")
      (node (ref "P4") (pin "4") (pinfunction "4_4") (pintype "passive"))
      (node (ref "U1") (pin "95") (pinfunction "PB15_95") (pintype "passive"))
    )
    (net (code "18") (name "/CT_INT") (class "Default")
      (node (ref "J1") (pin "1") (pinfunction "INT_1") (pintype "passive"))
      (node (ref "U1") (pin "101") (pinfunction "PD13_101") (pintype "passive"))
    )
    (net (code "19") (name "/CT_RST") (class "Default")
      (node (ref "J1") (pin "4") (pinfunction "RST_4") (pintype "passive"))
      (node (ref "U1") (pin "99") (pinfunction "PD11_99") (pintype "passive"))
    )
    (net (code "20") (name "/CT_SCL") (class "Default")
      (node (ref "J1") (pin "3") (pinfunction "SCL_3") (pintype "passive"))
      (node (ref "R20") (pin "1") (pinfunction "1_1") (pintype "passive"))
      (node (ref "U1") (pin "45") (pinfunction "PH4_45") (pintype "passive"))
    )
    (net (code "21") (name "/CT_SDA") (class "Default")
      (node (ref "J1") (pin "2") (pinfunction "SDA_2") (pintype "passive"))
      (node (ref "R19") (pin "1") (pinfunction "1_1") (pintype "passive"))
      (node (ref "U1") (pin "46") (pinfunction "PH5_46") (pintype "passive"))
    )
    (net (code "22") (name "/DATA_A") (class "Default")
      (node (ref "P3") (pin "3") (pinfunction "3_3") (pintype "passive"))
      (node (ref "U1") (pin "40") (pinfunction "PA0_40") (pintype "passive"))
    )
    (net (code "23") (name "/DATA_B") (class "Default")
      (node (ref "P3") (pin "4") (pinfunction "4_4") (pintype "passive"))
      (node (ref "U1") (pin "41") (pinfunction "PA1_41") (pintype "passive"))
    )
    (net (code "24") (name "/DATA_C") (class "Default")
      (node (ref "P3") (pin "5") (pinfunction "5_5") (pintype "passive"))
      (node (ref "U1") (pin "54") (pinfunction "PC4_54") (pintype "passive"))
    )
    (net (code "25") (name "/DCLK") (class "Default")
      (node (ref "J2") (pin "37") (pinfunction "DCLK_37") (pintype "passive"))
      (node (ref "RP7") (pin "1") (pinfunction "1_1") (pintype "passive"))
    )
    (net (code "26") (name "/DEN") (class "Default")
      (node (ref "J2") (pin "9") (pinfunction "DEN_9") (pintype "passive"))
      (node (ref "RP7") (pin "4") (pinfunction "4_4") (pintype "passive"))
    )
    (net (code "27") (name "/DIO") (class "Default")
      (node (ref "U1") (pin "27") (pinfunction "PF9_27") (pintype "passive"))
      (node (ref "U3") (pin "5") (pinfunction "DIO_5") (pintype "passive"))
    )
    (net (code "28") (name "/DITHB") (class "Default")
      (node (ref "J2") (pin "47") (pinfunction "DITHB_47") (pintype "passive"))
      (node (ref "R17") (pin "1") (pinfunction "1_1") (pintype "passive"))
      (node (ref "R18") (pin "1") (pinfunction "1_1") (pintype "passive"))
    )
    (net (code "29") (name "/DO") (class "Default")
      (node (ref "U1") (pin "26") (pinfunction "PF8_26") (pintype "passive"))
      (node (ref "U3") (pin "2") (pinfunction "DO_2") (pintype "passive"))
    )
    (net (code "30") (name "/FB") (class "Default")
      (node (ref "R13") (pin "1") (pinfunction "1_1") (pintype "passive"))
      (node (ref "R21") (pin "2") (pinfunction "2_2") (pintype "passive"))
      (node (ref "U6") (pin "3") (pinfunction "FB_3") (pintype "passive"))
    )
    (net (code "31") (name "/FSMC_A0") (class "Default")
      (node (ref "U1") (pin "16") (pinfunction "PF0_16") (pintype "passive"))
      (node (ref "U2") (pin "23") (pinfunction "A0_23") (pintype "passive"))
    )
    (net (code "32") (name "/FSMC_A1") (class "Default")
      (node (ref "U1") (pin "17") (pinfunction "PF1_17") (pintype "passive"))
      (node (ref "U2") (pin "24") (pinfunction "A1_24") (pintype "passive"))
    )
    (net (code "33") (name "/FSMC_A2") (class "Default")
      (node (ref "U1") (pin "18") (pinfunction "PF2_18") (pintype "passive"))
      (node (ref "U2") (pin "25") (pinfunction "A2_25") (pintype "passive"))
    )
    (net (code "34") (name "/FSMC_A3") (class "Default")
      (node (ref "U1") (pin "19") (pinfunction "PF3_19") (pintype "passive"))
      (node (ref "U2") (pin "26") (pinfunction "A3_26") (pintype "passive"))
    )
    (net (code "35") (name "/FSMC_A4") (class "Default")
      (node (ref "U1") (pin "20") (pinfunction "PF4_20") (pintype "passive"))
      (node (ref "U2") (pin "29") (pinfunction "A4_29") (pintype "passive"))
    )
    (net (code "36") (name "/FSMC_A5") (class "Default")
      (node (ref "U1") (pin "21") (pinfunction "PF5_21") (pintype "passive"))
      (node (ref "U2") (pin "30") (pinfunction "A5_30") (pintype "passive"))
    )
    (net (code "37") (name "/FSMC_A6") (class "Default")
      (node (ref "U1") (pin "60") (pinfunction "PF12_60") (pintype "passive"))
      (node (ref "U2") (pin "31") (pinfunction "A6_31") (pintype "passive"))
    )
    (net (code "38") (name "/FSMC_A7") (class "Default")
      (node (ref "U1") (pin "63") (pinfunction "PF13_63") (pintype "passive"))
      (node (ref "U2") (pin "32") (pinfunction "A7_32") (pintype "passive"))
    )
    (net (code "39") (name "/FSMC_A8") (class "Default")
      (node (ref "U1") (pin "64") (pinfunction "PF14_64") (pintype "passive"))
      (node (ref "U2") (pin "33") (pinfunction "A8_33") (pintype "passive"))
    )
    (net (code "40") (name "/FSMC_A9") (class "Default")
      (node (ref "U1") (pin "65") (pinfunction "PF15_65") (pintype "passive"))
      (node (ref "U2") (pin "34") (pinfunction "A9_34") (pintype "passive"))
    )
    (net (code "41") (name "/FSMC_A10") (class "Default")
      (node (ref "U1") (pin "66") (pinfunction "PG0_66") (pintype "passive"))
      (node (ref "U2") (pin "22") (pinfunction "A10_22") (pintype "passive"))
    )
    (net (code "42") (name "/FSMC_A11") (class "Default")
      (node (ref "U1") (pin "67") (pinfunction "PG1_67") (pintype "passive"))
      (node (ref "U2") (pin "35") (pinfunction "A11_35") (pintype "passive"))
    )
    (net (code "43") (name "/FSMC_A14_BA0") (class "Default")
      (node (ref "U1") (pin "108") (pinfunction "PG4_108") (pintype "passive"))
      (node (ref "U2") (pin "20") (pinfunction "BA0_20") (pintype "passive"))
    )
    (net (code "44") (name "/FSMC_A15_BA1") (class "Default")
      (node (ref "U1") (pin "109") (pinfunction "PG5_109") (pintype "passive"))
      (node (ref "U2") (pin "21") (pinfunction "BA1_21") (pintype "passive"))
    )
    (net (code "45") (name "/FSMC_D0_DA0") (class "Default")
      (node (ref "U1") (pin "104") (pinfunction "PD14_104") (pintype "passive"))
      (node (ref "U2") (pin "2") (pinfunction "DQ0_2") (pintype "passive"))
    )
    (net (code "46") (name "/FSMC_D0_DA1") (class "Default")
      (node (ref "U1") (pin "105") (pinfunction "PD15_105") (pintype "passive"))
      (node (ref "U2") (pin "4") (pinfunction "DQ1_4") (pintype "passive"))
    )
    (net (code "47") (name "/FSMC_D0_DA2") (class "Default")
      (node (ref "U1") (pin "142") (pinfunction "PD0_142") (pintype "passive"))
      (node (ref "U2") (pin "5") (pinfunction "DQ2_5") (pintype "passive"))
    )
    (net (code "48") (name "/FSMC_D0_DA3") (class "Default")
      (node (ref "U1") (pin "143") (pinfunction "PD1_143") (pintype "passive"))
      (node (ref "U2") (pin "7") (pinfunction "DQ3_7") (pintype "passive"))
    )
    (net (code "49") (name "/FSMC_D0_DA4") (class "Default")
      (node (ref "U1") (pin "68") (pinfunction "PE7_68") (pintype "passive"))
      (node (ref "U2") (pin "8") (pinfunction "DQ4_8") (pintype "passive"))
    )
    (net (code "50") (name "/FSMC_D0_DA5") (class "Default")
      (node (ref "U1") (pin "69") (pinfunction "PE8_69") (pintype "passive"))
      (node (ref "U2") (pin "10") (pinfunction "DQ5_10") (pintype "passive"))
    )
    (net (code "51") (name "/FSMC_D0_DA6") (class "Default")
      (node (ref "U1") (pin "70") (pinfunction "PE9_70") (pintype "passive"))
      (node (ref "U2") (pin "11") (pinfunction "DQ6_11") (pintype "passive"))
    )
    (net (code "52") (name "/FSMC_D0_DA7") (class "Default")
      (node (ref "U1") (pin "73") (pinfunction "PE10_73") (pintype "passive"))
      (node (ref "U2") (pin "13") (pinfunction "DQ7_13") (pintype "passive"))
    )
    (net (code "53") (name "/FSMC_D0_DA8") (class "Default")
      (node (ref "U1") (pin "74") (pinfunction "PE11_74") (pintype "passive"))
      (node (ref "U2") (pin "42") (pinfunction "DQ8_42") (pintype "passive"))
    )
    (net (code "54") (name "/FSMC_D0_DA9") (class "Default")
      (node (ref "U1") (pin "75") (pinfunction "PE12_75") (pintype "passive"))
      (node (ref "U2") (pin "44") (pinfunction "DQ9_44") (pintype "passive"))
    )
    (net (code "55") (name "/FSMC_D0_DA10") (class "Default")
      (node (ref "U1") (pin "76") (pinfunction "PE13_76") (pintype "passive"))
      (node (ref "U2") (pin "45") (pinfunction "DQ10_45") (pintype "passive"))
    )
    (net (code "56") (name "/FSMC_D0_DA11") (class "Default")
      (node (ref "U1") (pin "77") (pinfunction "PE14_77") (pintype "passive"))
      (node (ref "U2") (pin "47") (pinfunction "DQ11_47") (pintype "passive"))
    )
    (net (code "57") (name "/FSMC_D0_DA12") (class "Default")
      (node (ref "U1") (pin "78") (pinfunction "PE15_78") (pintype "passive"))
      (node (ref "U2") (pin "48") (pinfunction "DQ12_48") (pintype "passive"))
    )
    (net (code "58") (name "/FSMC_D0_DA13") (class "Default")
      (node (ref "U1") (pin "96") (pinfunction "PD8_96") (pintype "passive"))
      (node (ref "U2") (pin "50") (pinfunction "DQ13_50") (pintype "passive"))
    )
    (net (code "59") (name "/FSMC_D0_DA14") (class "Default")
      (node (ref "U1") (pin "97") (pinfunction "PD9_97") (pintype "passive"))
      (node (ref "U2") (pin "51") (pinfunction "DQ14_51") (pintype "passive"))
    )
    (net (code "60") (name "/FSMC_D0_DA15") (class "Default")
      (node (ref "U1") (pin "98") (pinfunction "PD10_98") (pintype "passive"))
      (node (ref "U2") (pin "53") (pinfunction "DQ15_53") (pintype "passive"))
    )
    (net (code "61") (name "/FSMC_NBL0") (class "Default")
      (node (ref "U1") (pin "169") (pinfunction "PE0_169") (pintype "passive"))
      (node (ref "U2") (pin "15") (pinfunction "LDQM_15") (pintype "passive"))
    )
    (net (code "62") (name "/FSMC_NBL1") (class "Default")
      (node (ref "U1") (pin "170") (pinfunction "PE1_170") (pintype "passive"))
      (node (ref "U2") (pin "39") (pinfunction "UDQM_39") (pintype "passive"))
    )
    (net (code "63") (name "/FSMC_SCLK") (class "Default")
      (node (ref "U1") (pin "112") (pinfunction "PG8_112") (pintype "passive"))
      (node (ref "U2") (pin "38") (pinfunction "CLK_38") (pintype "passive"))
    )
    (net (code "64") (name "/FSMC_SDCKE1") (class "Default")
      (node (ref "U1") (pin "84") (pinfunction "PH7_84") (pintype "passive"))
      (node (ref "U2") (pin "37") (pinfunction "CKE_37") (pintype "passive"))
    )
    (net (code "65") (name "/FSMC_SDNCAS") (class "Default")
      (node (ref "U1") (pin "160") (pinfunction "PG15_160") (pintype "passive"))
      (node (ref "U2") (pin "17") (pinfunction "CAS#_17") (pintype "passive"))
    )
    (net (code "66") (name "/FSMC_SDNE1") (class "Default")
      (node (ref "R4") (pin "2") (pinfunction "2_2") (pintype "passive"))
      (node (ref "U1") (pin "83") (pinfunction "PH6_83") (pintype "passive"))
      (node (ref "U2") (pin "19") (pinfunction "CS#_19") (pintype "passive"))
    )
    (net (code "67") (name "/FSMC_SDNRAS") (class "Default")
      (node (ref "U1") (pin "59") (pinfunction "PF11_59") (pintype "passive"))
      (node (ref "U2") (pin "18") (pinfunction "RAS#_18") (pintype "passive"))
    )
    (net (code "68") (name "/FSMC_SDNWE") (class "Default")
      (node (ref "U1") (pin "32") (pinfunction "PC0_32") (pintype "passive"))
      (node (ref "U2") (pin "16") (pinfunction "WE#_16") (pintype "passive"))
    )
    (net (code "69") (name "/G0") (class "Default")
      (node (ref "J2") (pin "27") (pinfunction "G0_27") (pintype "passive"))
      (node (ref "RP5") (pin "1") (pinfunction "1_1") (pintype "passive"))
    )
    (net (code "70") (name "/G1") (class "Default")
      (node (ref "J2") (pin "26") (pinfunction "G1_26") (pintype "passive"))
      (node (ref "RP5") (pin "2") (pinfunction "2_2") (pintype "passive"))
    )
    (net (code "71") (name "/G2") (class "Default")
      (node (ref "J2") (pin "25") (pinfunction "G2_25") (pintype "passive"))
      (node (ref "RP5") (pin "3") (pinfunction "3_3") (pintype "passive"))
    )
    (net (code "72") (name "/G3") (class "Default")
      (node (ref "J2") (pin "24") (pinfunction "G3_24") (pintype "passive"))
      (node (ref "RP5") (pin "4") (pinfunction "4_4") (pintype "passive"))
    )
    (net (code "73") (name "/G4") (class "Default")
      (node (ref "J2") (pin "23") (pinfunction "G4_23") (pintype "passive"))
      (node (ref "RP6") (pin "1") (pinfunction "1_1") (pintype "passive"))
    )
    (net (code "74") (name "/G5") (class "Default")
      (node (ref "J2") (pin "22") (pinfunction "G5_22") (pintype "passive"))
      (node (ref "RP6") (pin "2") (pinfunction "2_2") (pintype "passive"))
    )
    (net (code "75") (name "/G6") (class "Default")
      (node (ref "J2") (pin "21") (pinfunction "G6_21") (pintype "passive"))
      (node (ref "RP6") (pin "3") (pinfunction "3_3") (pintype "passive"))
    )
    (net (code "76") (name "/G7") (class "Default")
      (node (ref "J2") (pin "20") (pinfunction "G7_20") (pintype "passive"))
      (node (ref "RP6") (pin "4") (pinfunction "4_4") (pintype "passive"))
    )
    (net (code "77") (name "/HSYNC") (class "Default")
      (node (ref "J2") (pin "11") (pinfunction "HSYNC_11") (pintype "passive"))
      (node (ref "RP7") (pin "2") (pinfunction "2_2") (pintype "passive"))
    )
    (net (code "78") (name "/JTCK") (class "Default")
      (node (ref "P2") (pin "2") (pinfunction "2_2") (pintype "passive"))
      (node (ref "U1") (pin "137") (pinfunction "PA14_137") (pintype "passive"))
    )
    (net (code "79") (name "/JTMS") (class "Default")
      (node (ref "P2") (pin "3") (pinfunction "3_3") (pintype "passive"))
      (node (ref "U1") (pin "124") (pinfunction "PA13_124") (pintype "passive"))
    )
    (net (code "80") (name "/LEDA") (class "Default")
      (node (ref "C52") (pin "2") (pinfunction "2_2") (pintype "passive"))
      (node (ref "D4") (pin "2") (pinfunction "K_2") (pintype "passive"))
      (node (ref "J2") (pin "1") (pinfunction "A_1") (pintype "passive"))
      (node (ref "J2") (pin "2") (pinfunction "A_2") (pintype "passive"))
    )
    (net (code "81") (name "/LEDK") (class "Default")
      (node (ref "J2") (pin "3") (pinfunction "K_3") (pintype "passive"))
      (node (ref "J2") (pin "4") (pinfunction "K_4") (pintype "passive"))
      (node (ref "R28") (pin "2") (pinfunction "2_2") (pintype "passive"))
      (node (ref "U8") (pin "3") (pinfunction "FB_3") (pintype "passive"))
    )
    (net (code "82") (name "/LR") (class "Default")
      (node (ref "J2") (pin "39") (pinfunction "LR_39") (pintype "passive"))
      (node (ref "R24") (pin "1") (pinfunction "1_1") (pintype "passive"))
      (node (ref "R25") (pin "1") (pinfunction "1_1") (pintype "passive"))
    )
    (net (code "83") (name "/LTDC_B0") (class "Default")
      (node (ref "RP3") (pin "8") (pinfunction "8_8") (pintype "passive"))
      (node (ref "U1") (pin "3") (pinfunction "PE4_3") (pintype "passive"))
    )
    (net (code "84") (name "/LTDC_B1") (class "Default")
      (node (ref "RP3") (pin "7") (pinfunction "7_7") (pintype "passive"))
      (node (ref "U1") (pin "155") (pinfunction "PG12_155") (pintype "passive"))
    )
    (net (code "85") (name "/LTDC_B2") (class "Default")
      (node (ref "RP3") (pin "6") (pinfunction "6_6") (pintype "passive"))
      (node (ref "U1") (pin "150") (pinfunction "PD6_150") (pintype "passive"))
    )
    (net (code "86") (name "/LTDC_B3") (class "Default")
      (node (ref "RP3") (pin "5") (pinfunction "5_5") (pintype "passive"))
      (node (ref "U1") (pin "154") (pinfunction "PG11_154") (pintype "passive"))
    )
    (net (code "87") (name "/LTDC_B4") (class "Default")
      (node (ref "RP4") (pin "8") (pinfunction "8_8") (pintype "passive"))
      (node (ref "U1") (pin "173") (pinfunction "PI4_173") (pintype "passive"))
    )
    (net (code "88") (name "/LTDC_B5") (class "Default")
      (node (ref "RP4") (pin "7") (pinfunction "7_7") (pintype "passive"))
      (node (ref "U1") (pin "47") (pinfunction "PA3_47") (pintype "passive"))
    )
    (net (code "89") (name "/LTDC_B6") (class "Default")
      (node (ref "RP4") (pin "6") (pinfunction "6_6") (pintype "passive"))
      (node (ref "U1") (pin "167") (pinfunction "PB8_167") (pintype "passive"))
    )
    (net (code "90") (name "/LTDC_B7") (class "Default")
      (node (ref "RP4") (pin "5") (pinfunction "5_5") (pintype "passive"))
      (node (ref "U1") (pin "168") (pinfunction "PB9_168") (pintype "passive"))
    )
    (net (code "91") (name "/LTDC_CLK") (class "Default")
      (node (ref "RP7") (pin "8") (pinfunction "8_8") (pintype "passive"))
      (node (ref "U1") (pin "111") (pinfunction "PG7_111") (pintype "passive"))
    )
    (net (code "92") (name "/LTDC_DE") (class "Default")
      (node (ref "RP7") (pin "5") (pinfunction "5_5") (pintype "passive"))
      (node (ref "U1") (pin "28") (pinfunction "PF10_28") (pintype "passive"))
    )
    (net (code "93") (name "/LTDC_G0") (class "Default")
      (node (ref "RP5") (pin "8") (pinfunction "8_8") (pintype "passive"))
      (node (ref "U1") (pin "4") (pinfunction "PE5_4") (pintype "passive"))
    )
    (net (code "94") (name "/LTDC_G1") (class "Default")
      (node (ref "RP5") (pin "7") (pinfunction "7_7") (pintype "passive"))
      (node (ref "U1") (pin "5") (pinfunction "PE6_5") (pintype "passive"))
    )
    (net (code "95") (name "/LTDC_G2") (class "Default")
      (node (ref "RP5") (pin "6") (pinfunction "6_6") (pintype "passive"))
      (node (ref "U1") (pin "128") (pinfunction "PH13_128") (pintype "passive"))
    )
    (net (code "96") (name "/LTDC_G3") (class "Default")
      (node (ref "RP5") (pin "5") (pinfunction "5_5") (pintype "passive"))
      (node (ref "U1") (pin "153") (pinfunction "PG10_153") (pintype "passive"))
    )
    (net (code "97") (name "/LTDC_G4") (class "Default")
      (node (ref "RP6") (pin "8") (pinfunction "8_8") (pintype "passive"))
      (node (ref "U1") (pin "130") (pinfunction "PH15_130") (pintype "passive"))
    )
    (net (code "98") (name "/LTDC_G5") (class "Default")
      (node (ref "RP6") (pin "7") (pinfunction "7_7") (pintype "passive"))
      (node (ref "U1") (pin "131") (pinfunction "PI0_131") (pintype "passive"))
    )
    (net (code "99") (name "/LTDC_G6") (class "Default")
      (node (ref "RP6") (pin "6") (pinfunction "6_6") (pintype "passive"))
      (node (ref "U1") (pin "116") (pinfunction "PC7_116") (pintype "passive"))
    )
    (net (code "100") (name "/LTDC_G7") (class "Default")
      (node (ref "RP6") (pin "5") (pinfunction "5_5") (pintype "passive"))
      (node (ref "U1") (pin "133") (pinfunction "PI2_133") (pintype "passive"))
    )
    (net (code "101") (name "/LTDC_HSYNC") (class "Default")
      (node (ref "RP7") (pin "7") (pinfunction "7_7") (pintype "passive"))
      (node (ref "U1") (pin "12") (pinfunction "PI10_12") (pintype "passive"))
    )
    (net (code "102") (name "/LTDC_R0") (class "Default")
      (node (ref "RP1") (pin "8") (pinfunction "8_8") (pintype "passive"))
      (node (ref "U1") (pin "43") (pinfunction "PH2_43") (pintype "passive"))
    )
    (net (code "103") (name "/LTDC_R1") (class "Default")
      (node (ref "RP1") (pin "7") (pinfunction "7_7") (pintype "passive"))
      (node (ref "U1") (pin "44") (pinfunction "PH3_44") (pintype "passive"))
    )
    (net (code "104") (name "/LTDC_R2") (class "Default")
      (node (ref "RP1") (pin "6") (pinfunction "6_6") (pintype "passive"))
      (node (ref "U1") (pin "85") (pinfunction "PH8_85") (pintype "passive"))
    )
    (net (code "105") (name "/LTDC_R3") (class "Default")
      (node (ref "RP1") (pin "5") (pinfunction "5_5") (pintype "passive"))
      (node (ref "U1") (pin "56") (pinfunction "PB0_56") (pintype "passive"))
    )
    (net (code "106") (name "/LTDC_R4") (class "Default")
      (node (ref "RP2") (pin "8") (pinfunction "8_8") (pintype "passive"))
      (node (ref "U1") (pin "122") (pinfunction "PA11_122") (pintype "passive"))
    )
    (net (code "107") (name "/LTDC_R5") (class "Default")
      (node (ref "RP2") (pin "7") (pinfunction "7_7") (pintype "passive"))
      (node (ref "U1") (pin "123") (pinfunction "PA12_123") (pintype "passive"))
    )
    (net (code "108") (name "/LTDC_R6") (class "Default")
      (node (ref "RP2") (pin "6") (pinfunction "6_6") (pintype "passive"))
      (node (ref "U1") (pin "57") (pinfunction "PB1_57") (pintype "passive"))
    )
    (net (code "109") (name "/LTDC_R7") (class "Default")
      (node (ref "RP2") (pin "5") (pinfunction "5_5") (pintype "passive"))
      (node (ref "U1") (pin "110") (pinfunction "PG6_110") (pintype "passive"))
    )
    (net (code "110") (name "/LTDC_VSYNC") (class "Default")
      (node (ref "RP7") (pin "6") (pinfunction "6_6") (pintype "passive"))
      (node (ref "U1") (pin "11") (pinfunction "PI9_11") (pintype "passive"))
    )
    (net (code "111") (name "/LX") (class "Default")
      (node (ref "C30") (pin "2") (pinfunction "2_2") (pintype "passive"))
      (node (ref "C36") (pin "2") (pinfunction "2_2") (pintype "passive"))
      (node (ref "D3") (pin "1") (pinfunction "A_1") (pintype "passive"))
      (node (ref "L2") (pin "2") (pinfunction "2_2") (pintype "passive"))
      (node (ref "U6") (pin "1") (pinfunction "SW_1") (pintype "passive"))
    )
    (net (code "112") (name "/MODE") (class "Default")
      (node (ref "J2") (pin "8") (pinfunction "MODE_8") (pintype "passive"))
      (node (ref "R12") (pin "1") (pinfunction "1_1") (pintype "passive"))
      (node (ref "R16") (pin "1") (pinfunction "1_1") (pintype "passive"))
    )
    (net (code "113") (name "/NCS") (class "Default")
      (node (ref "R5") (pin "2") (pinfunction "2_2") (pintype "passive"))
      (node (ref "U1") (pin "24") (pinfunction "PF6_24") (pintype "passive"))
      (node (ref "U3") (pin "1") (pinfunction "C~{S}_1") (pintype "passive"))
    )
    (net (code "114") (name "/NRST") (class "Default")
      (node (ref "C1") (pin "1") (pinfunction "1_1") (pintype "passive"))
      (node (ref "R1") (pin "1") (pinfunction "1_1") (pintype "passive"))
      (node (ref "S1") (pin "1") (pinfunction "1_1") (pintype "passive"))
      (node (ref "U1") (pin "31") (pinfunction "NRST_31") (pintype "passive"))
    )
    (net (code "115") (name "/OSC_IN") (class "Default")
      (node (ref "C4") (pin "1") (pinfunction "1_1") (pintype "passive"))
      (node (ref "U1") (pin "29") (pinfunction "PH0_29") (pintype "passive"))
      (node (ref "Y1") (pin "2") (pinfunction "OSC2_2") (pintype "passive"))
    )
    (net (code "116") (name "/OSC_OUT") (class "Default")
      (node (ref "C8") (pin "1") (pinfunction "1_1") (pintype "passive"))
      (node (ref "U1") (pin "30") (pinfunction "PH1_30") (pintype "passive"))
      (node (ref "Y1") (pin "1") (pinfunction "OSC1_1") (pintype "passive"))
    )
    (net (code "117") (name "/R0") (class "Default")
      (node (ref "J2") (pin "35") (pinfunction "R0_35") (pintype "passive"))
      (node (ref "RP1") (pin "1") (pinfunction "1_1") (pintype "passive"))
    )
    (net (code "118") (name "/R1") (class "Default")
      (node (ref "J2") (pin "34") (pinfunction "R1_34") (pintype "passive"))
      (node (ref "RP1") (pin "2") (pinfunction "2_2") (pintype "passive"))
    )
    (net (code "119") (name "/R2") (class "Default")
      (node (ref "J2") (pin "33") (pinfunction "R2_33") (pintype "passive"))
      (node (ref "RP1") (pin "3") (pinfunction "3_3") (pintype "passive"))
    )
    (net (code "120") (name "/R3") (class "Default")
      (node (ref "J2") (pin "32") (pinfunction "R3_32") (pintype "passive"))
      (node (ref "RP1") (pin "4") (pinfunction "4_4") (pintype "passive"))
    )
    (net (code "121") (name "/R4") (class "Default")
      (node (ref "J2") (pin "31") (pinfunction "R4_31") (pintype "passive"))
      (node (ref "RP2") (pin "1") (pinfunction "1_1") (pintype "passive"))
    )
    (net (code "122") (name "/R5") (class "Default")
      (node (ref "J2") (pin "30") (pinfunction "R5_30") (pintype "passive"))
      (node (ref "RP2") (pin "2") (pinfunction "2_2") (pintype "passive"))
    )
    (net (code "123") (name "/R6") (class "Default")
      (node (ref "J2") (pin "29") (pinfunction "R6_29") (pintype "passive"))
      (node (ref "RP2") (pin "3") (pinfunction "3_3") (pintype "passive"))
    )
    (net (code "124") (name "/R7") (class "Default")
      (node (ref "J2") (pin "28") (pinfunction "R7_28") (pintype "passive"))
      (node (ref "RP2") (pin "4") (pinfunction "4_4") (pintype "passive"))
    )
    (net (code "125") (name "/RESET") (class "Default")
      (node (ref "C41") (pin "2") (pinfunction "2_2") (pintype "passive"))
      (node (ref "J2") (pin "44") (pinfunction "RESET_44") (pintype "passive"))
      (node (ref "R9") (pin "2") (pinfunction "2_2") (pintype "passive"))
    )
    (net (code "126") (name "/ROW0") (class "Default")
      (node (ref "P4") (pin "5") (pinfunction "5_5") (pintype "passive"))
      (node (ref "U1") (pin "50") (pinfunction "PA4_50") (pintype "passive"))
    )
    (net (code "127") (name "/ROW1") (class "Default")
      (node (ref "P4") (pin "6") (pinfunction "6_6") (pintype "passive"))
      (node (ref "U1") (pin "51") (pinfunction "PA5_51") (pintype "passive"))
    )
    (net (code "128") (name "/ROW2") (class "Default")
      (node (ref "P4") (pin "7") (pinfunction "7_7") (pintype "passive"))
      (node (ref "U1") (pin "52") (pinfunction "PA6_52") (pintype "passive"))
    )
    (net (code "129") (name "/ROW3") (class "Default")
      (node (ref "P4") (pin "8") (pinfunction "8_8") (pintype "passive"))
      (node (ref "U1") (pin "53") (pinfunction "PA7_53") (pintype "passive"))
    )
    (net (code "130") (name "/SDIO_CK") (class "Default")
      (node (ref "TF1") (pin "5") (pinfunction "SCLK_5") (pintype "passive"))
      (node (ref "U1") (pin "141") (pinfunction "PC12_141") (pintype "passive"))
    )
    (net (code "131") (name "/SDIO_CMD") (class "Default")
      (node (ref "R33") (pin "1") (pinfunction "1_1") (pintype "passive"))
      (node (ref "TF1") (pin "3") (pinfunction "DI_3") (pintype "passive"))
      (node (ref "U1") (pin "144") (pinfunction "PD2_144") (pintype "passive"))
    )
    (net (code "132") (name "/SDIO_D0") (class "Default")
      (node (ref "R29") (pin "1") (pinfunction "1_1") (pintype "passive"))
      (node (ref "TF1") (pin "7") (pinfunction "DO_7") (pintype "passive"))
      (node (ref "U1") (pin "117") (pinfunction "PC8_117") (pintype "passive"))
    )
    (net (code "133") (name "/SDIO_D1") (class "Default")
      (node (ref "R30") (pin "1") (pinfunction "1_1") (pintype "passive"))
      (node (ref "TF1") (pin "8") (pinfunction "RSV_8") (pintype "passive"))
      (node (ref "U1") (pin "118") (pinfunction "PC9_118") (pintype "passive"))
    )
    (net (code "134") (name "/SDIO_D2") (class "Default")
      (node (ref "R31") (pin "1") (pinfunction "1_1") (pintype "passive"))
      (node (ref "TF1") (pin "1") (pinfunction "RSV_1") (pintype "passive"))
      (node (ref "U1") (pin "139") (pinfunction "PC10_139") (pintype "passive"))
    )
    (net (code "135") (name "/SDIO_D3") (class "Default")
      (node (ref "R32") (pin "1") (pinfunction "1_1") (pintype "passive"))
      (node (ref "TF1") (pin "2") (pinfunction "CS_2") (pintype "passive"))
      (node (ref "U1") (pin "140") (pinfunction "PC11_140") (pintype "passive"))
    )
    (net (code "136") (name "/UD") (class "Default")
      (node (ref "J2") (pin "40") (pinfunction "UD_40") (pintype "passive"))
      (node (ref "R22") (pin "1") (pinfunction "1_1") (pintype "passive"))
      (node (ref "R23") (pin "1") (pinfunction "1_1") (pintype "passive"))
    )
    (net (code "137") (name "/USART1_RX") (class "Default")
      (node (ref "P1") (pin "4") (pinfunction "4_4") (pintype "passive"))
      (node (ref "U1") (pin "121") (pinfunction "PA10_121") (pintype "passive"))
    )
    (net (code "138") (name "/USART1_TX") (class "Default")
      (node (ref "P1") (pin "3") (pinfunction "3_3") (pintype "passive"))
      (node (ref "U1") (pin "120") (pinfunction "PA9_120") (pintype "passive"))
    )
    (net (code "139") (name "/USART3_RX") (class "Default")
      (node (ref "P5") (pin "3") (pinfunction "3_3") (pintype "passive"))
      (node (ref "U1") (pin "80") (pinfunction "PB11_80") (pintype "passive"))
    )
    (net (code "140") (name "/USART3_TX") (class "Default")
      (node (ref "P5") (pin "2") (pinfunction "2_2") (pintype "passive"))
      (node (ref "U1") (pin "79") (pinfunction "PB10_79") (pintype "passive"))
    )
    (net (code "141") (name "/VCOM") (class "Default")
      (node (ref "C42") (pin "2") (pinfunction "2_2") (pintype "passive"))
      (node (ref "C43") (pin "2") (pinfunction "2_2") (pintype "passive"))
      (node (ref "J2") (pin "46") (pinfunction "VCOM_46") (pintype "passive"))
      (node (ref "J2") (pin "6") (pinfunction "VCOM_6") (pintype "passive"))
      (node (ref "R10") (pin "2") (pinfunction "2_2") (pintype "passive"))
      (node (ref "R11") (pin "1") (pinfunction "1_1") (pintype "passive"))
    )
    (net (code "142") (name "/VGH") (class "Default")
      (node (ref "C32") (pin "1") (pinfunction "1_1") (pintype "passive"))
      (node (ref "C33") (pin "1") (pinfunction "1_1") (pintype "passive"))
      (node (ref "C34") (pin "1") (pinfunction "1_1") (pintype "passive"))
      (node (ref "D1") (pin "2") (pinfunction "K_2") (pintype "passive"))
      (node (ref "J2") (pin "41") (pinfunction "VGH_41") (pintype "passive"))
      (node (ref "R6") (pin "2") (pinfunction "2_2") (pintype "passive"))
    )
    (net (code "143") (name "/VGL") (class "Default")
      (node (ref "C38") (pin "1") (pinfunction "1_1") (pintype "passive"))
      (node (ref "C39") (pin "1") (pinfunction "1_1") (pintype "passive"))
      (node (ref "C40") (pin "1") (pinfunction "1_1") (pintype "passive"))
      (node (ref "D2") (pin "1") (pinfunction "A_1") (pintype "passive"))
      (node (ref "J2") (pin "42") (pinfunction "VGL_42") (pintype "passive"))
      (node (ref "R7") (pin "2") (pinfunction "2_2") (pintype "passive"))
      (node (ref "R8") (pin "2") (pinfunction "2_2") (pintype "passive"))
    )
    (net (code "144") (name "/VSYNC") (class "Default")
      (node (ref "J2") (pin "10") (pinfunction "VSYNC_10") (pintype "passive"))
      (node (ref "RP7") (pin "3") (pinfunction "3_3") (pintype "passive"))
    )
    (net (code "145") (name "GND") (class "Default")
      (node (ref "C1") (pin "2") (pinfunction "2_2") (pintype "passive"))
      (node (ref "C10") (pin "1") (pinfunction "1_1") (pintype "passive"))
      (node (ref "C11") (pin "1") (pinfunction "1_1") (pintype "passive"))
      (node (ref "C12") (pin "1") (pinfunction "1_1") (pintype "passive"))
      (node (ref "C13") (pin "2") (pinfunction "2_2") (pintype "passive"))
      (node (ref "C14") (pin "2") (pinfunction "2_2") (pintype "passive"))
      (node (ref "C15") (pin "2") (pinfunction "2_2") (pintype "passive"))
      (node (ref "C16") (pin "2") (pinfunction "2_2") (pintype "passive"))
      (node (ref "C17") (pin "2") (pinfunction "2_2") (pintype "passive"))
      (node (ref "C18") (pin "2") (pinfunction "2_2") (pintype "passive"))
      (node (ref "C19") (pin "2") (pinfunction "2_2") (pintype "passive"))
      (node (ref "C2") (pin "1") (pinfunction "1_1") (pintype "passive"))
      (node (ref "C20") (pin "2") (pinfunction "2_2") (pintype "passive"))
      (node (ref "C21") (pin "2") (pinfunction "2_2") (pintype "passive"))
      (node (ref "C22") (pin "2") (pinfunction "2_2") (pintype "passive"))
      (node (ref "C23") (pin "2") (pinfunction "2_2") (pintype "passive"))
      (node (ref "C24") (pin "2") (pinfunction "2_2") (pintype "passive"))
      (node (ref "C25") (pin "2") (pinfunction "2_2") (pintype "passive"))
      (node (ref "C26") (pin "2") (pinfunction "2_2") (pintype "passive"))
      (node (ref "C27") (pin "2") (pinfunction "2_2") (pintype "passive"))
      (node (ref "C28") (pin "1") (pinfunction "1_1") (pintype "passive"))
      (node (ref "C29") (pin "1") (pinfunction "1_1") (pintype "passive"))
      (node (ref "C3") (pin "1") (pinfunction "1_1") (pintype "passive"))
      (node (ref "C31") (pin "2") (pinfunction "2_2") (pintype "passive"))
      (node (ref "C32") (pin "2") (pinfunction "2_2") (pintype "passive"))
      (node (ref "C33") (pin "2") (pinfunction "2_2") (pintype "passive"))
      (node (ref "C34") (pin "2") (pinfunction "2_2") (pintype "passive"))
      (node (ref "C35") (pin "1") (pinfunction "1_1") (pintype "passive"))
      (node (ref "C37") (pin "2") (pinfunction "2_2") (pintype "passive"))
      (node (ref "C38") (pin "2") (pinfunction "2_2") (pintype "passive"))
      (node (ref "C39") (pin "2") (pinfunction "2_2") (pintype "passive"))
      (node (ref "C4") (pin "2") (pinfunction "2_2") (pintype "passive"))
      (node (ref "C40") (pin "2") (pinfunction "2_2") (pintype "passive"))
      (node (ref "C41") (pin "1") (pinfunction "1_1") (pintype "passive"))
      (node (ref "C42") (pin "1") (pinfunction "1_1") (pintype "passive"))
      (node (ref "C43") (pin "1") (pinfunction "1_1") (pintype "passive"))
      (node (ref "C44") (pin "1") (pinfunction "1_1") (pintype "passive"))
      (node (ref "C45") (pin "1") (pinfunction "1_1") (pintype "passive"))
      (node (ref "C46") (pin "1") (pinfunction "1_1") (pintype "passive"))
      (node (ref "C47") (pin "1") (pinfunction "1_1") (pintype "passive"))
      (node (ref "C48") (pin "1") (pinfunction "1_1") (pintype "passive"))
      (node (ref "C49") (pin "1") (pinfunction "1_1") (pintype "passive"))
      (node (ref "C5") (pin "1") (pinfunction "1_1") (pintype "passive"))
      (node (ref "C50") (pin "1") (pinfunction "1_1") (pintype "passive"))
      (node (ref "C51") (pin "1") (pinfunction "1_1") (pintype "passive"))
      (node (ref "C52") (pin "1") (pinfunction "1_1") (pintype "passive"))
      (node (ref "C53") (pin "2") (pinfunction "2_2") (pintype "passive"))
      (node (ref "C54") (pin "2") (pinfunction "2_2") (pintype "passive"))
      (node (ref "C55") (pin "2") (pinfunction "-_2") (pintype "passive"))
      (node (ref "C56") (pin "2") (pinfunction "-_2") (pintype "passive"))
      (node (ref "C57") (pin "1") (pinfunction "1_1") (pintype "passive"))
      (node (ref "C58") (pin "1") (pinfunction "1_1") (pintype "passive"))
      (node (ref "C6") (pin "1") (pinfunction "1_1") (pintype "passive"))
      (node (ref "C7") (pin "1") (pinfunction "1_1") (pintype "passive"))
      (node (ref "C8") (pin "2") (pinfunction "2_2") (pintype "passive"))
      (node (ref "C9") (pin "1") (pinfunction "1_1") (pintype "passive"))
      (node (ref "D1") (pin "1") (pinfunction "A_1") (pintype "passive"))
      (node (ref "D2") (pin "2") (pinfunction "K_2") (pintype "passive"))
      (node (ref "J1") (pin "5") (pinfunction "GND_5") (pintype "passive"))
      (node (ref "J2") (pin "36") (pinfunction "GND_36") (pintype "passive"))
      (node (ref "J2") (pin "38") (pinfunction "GND_38") (pintype "passive"))
      (node (ref "J2") (pin "48") (pinfunction "GND_48") (pintype "passive"))
      (node (ref "J2") (pin "5") (pinfunction "GND_5") (pintype "passive"))
      (node (ref "P1") (pin "5") (pinfunction "5_5") (pintype "passive"))
      (node (ref "P1") (pin "6") (pinfunction "6_6") (pintype "passive"))
      (node (ref "P2") (pin "1") (pinfunction "1_1") (pintype "passive"))
      (node (ref "P3") (pin "2") (pinfunction "2_2") (pintype "passive"))
      (node (ref "P5") (pin "4") (pinfunction "4_4") (pintype "passive"))
      (node (ref "R11") (pin "2") (pinfunction "2_2") (pintype "passive"))
      (node (ref "R14") (pin "1") (pinfunction "1_1") (pintype "passive"))
      (node (ref "R16") (pin "2") (pinfunction "2_2") (pintype "passive"))
      (node (ref "R18") (pin "2") (pinfunction "2_2") (pintype "passive"))
      (node (ref "R2") (pin "2") (pinfunction "2_2") (pintype "passive"))
      (node (ref "R21") (pin "1") (pinfunction "1_1") (pintype "passive"))
      (node (ref "R23") (pin "2") (pinfunction "2_2") (pintype "passive"))
      (node (ref "R25") (pin "2") (pinfunction "2_2") (pintype "passive"))
      (node (ref "R27") (pin "1") (pinfunction "1_1") (pintype "passive"))
      (node (ref "R28") (pin "1") (pinfunction "1_1") (pintype "passive"))
      (node (ref "R3") (pin "2") (pinfunction "2_2") (pintype "passive"))
      (node (ref "R8") (pin "1") (pinfunction "1_1") (pintype "passive"))
      (node (ref "S1") (pin "2") (pinfunction "2_2") (pintype "passive"))
      (node (ref "TF1") (pin "6") (pinfunction "GND_6") (pintype "passive"))
      (node (ref "U1") (pin "102") (pinfunction "VSS_102") (pintype "passive"))
      (node (ref "U1") (pin "113") (pinfunction "VSS_113") (pintype "passive"))
      (node (ref "U1") (pin "126") (pinfunction "VSS_126") (pintype "passive"))
      (node (ref "U1") (pin "135") (pinfunction "VSS_135") (pintype "passive"))
      (node (ref "U1") (pin "14") (pinfunction "VSS_14") (pintype "passive"))
      (node (ref "U1") (pin "148") (pinfunction "VSS_148") (pintype "passive"))
      (node (ref "U1") (pin "158") (pinfunction "VSS_158") (pintype "passive"))
      (node (ref "U1") (pin "22") (pinfunction "VSS_22") (pintype "passive"))
      (node (ref "U1") (pin "37") (pinfunction "VSSA_37") (pintype "passive"))
      (node (ref "U1") (pin "48") (pinfunction "BYPASS_REG_48") (pintype "passive"))
      (node (ref "U1") (pin "61") (pinfunction "VSS_61") (pintype "passive"))
      (node (ref "U1") (pin "71") (pinfunction "VSS_71") (pintype "passive"))
      (node (ref "U1") (pin "90") (pinfunction "VSS_90") (pintype "passive"))
      (node (ref "U2") (pin "12") (pinfunction "GNDQ_12") (pintype "passive"))
      (node (ref "U2") (pin "28") (pinfunction "GND_28") (pintype "passive"))
      (node (ref "U2") (pin "41") (pinfunction "GND_41") (pintype "passive"))
      (node (ref "U2") (pin "46") (pinfunction "GNDQ_46") (pintype "passive"))
      (node (ref "U2") (pin "52") (pinfunction "GNDQ_52") (pintype "passive"))
      (node (ref "U2") (pin "54") (pinfunction "GND_54") (pintype "passive"))
      (node (ref "U2") (pin "6") (pinfunction "GNDQ_6") (pintype "passive"))
      (node (ref "U3") (pin "4") (pinfunction "GND_4") (pintype "passive"))
      (node (ref "U5") (pin "2") (pinfunction "2_2") (pintype "passive"))
      (node (ref "U6") (pin "2") (pinfunction "GND_2") (pintype "passive"))
      (node (ref "U7") (pin "1") (pinfunction "GND_1") (pintype "power_in"))
      (node (ref "U8") (pin "2") (pinfunction "GND_2") (pintype "passive"))
    )
    (net (code "146") (name "Net-(C30-Pad1)") (class "Default")
      (node (ref "C30") (pin "1") (pinfunction "1_1") (pintype "passive"))
      (node (ref "U4") (pin "3") (pinfunction "3_3") (pintype "passive"))
    )
    (net (code "147") (name "Net-(C31-Pad1)") (class "Default")
      (node (ref "C31") (pin "1") (pinfunction "1_1") (pintype "passive"))
      (node (ref "R6") (pin "1") (pinfunction "1_1") (pintype "passive"))
      (node (ref "U4") (pin "2") (pinfunction "2_2") (pintype "passive"))
    )
    (net (code "148") (name "Net-(C36-Pad1)") (class "Default")
      (node (ref "C36") (pin "1") (pinfunction "1_1") (pintype "passive"))
      (node (ref "U5") (pin "3") (pinfunction "3_3") (pintype "passive"))
    )
    (net (code "149") (name "Net-(C37-Pad1)") (class "Default")
      (node (ref "C37") (pin "1") (pinfunction "1_1") (pintype "passive"))
      (node (ref "R7") (pin "1") (pinfunction "1_1") (pintype "passive"))
      (node (ref "U5") (pin "1") (pinfunction "1_1") (pintype "passive"))
    )
    (net (code "150") (name "Net-(D4-A)") (class "Default")
      (node (ref "D4") (pin "1") (pinfunction "A_1") (pintype "passive"))
      (node (ref "L3") (pin "2") (pinfunction "2_2") (pintype "passive"))
      (node (ref "U8") (pin "1") (pinfunction "SW_1") (pintype "passive"))
    )
    (net (code "151") (name "Net-(U1A-VCAP_1)") (class "Default")
      (node (ref "C2") (pin "2") (pinfunction "2_2") (pintype "passive"))
      (node (ref "U1") (pin "81") (pinfunction "VCAP_1_81") (pintype "passive"))
    )
    (net (code "152") (name "Net-(U1A-VCAP_2)") (class "Default")
      (node (ref "C3") (pin "2") (pinfunction "2_2") (pintype "passive"))
      (node (ref "U1") (pin "125") (pinfunction "VCAP_2_125") (pintype "passive"))
    )
    (net (code "153") (name "Net-(U1A-VDDA)") (class "Default")
      (node (ref "C5") (pin "2") (pinfunction "2_2") (pintype "passive"))
      (node (ref "C6") (pin "2") (pinfunction "2_2") (pintype "passive"))
      (node (ref "L1") (pin "1") (pinfunction "1_1") (pintype "passive"))
      (node (ref "U1") (pin "38") (pinfunction "VREF+_38") (pintype "passive"))
      (node (ref "U1") (pin "39") (pinfunction "VDDA_39") (pintype "passive"))
    )
    (net (code "154") (name "Net-(U6-EN)") (class "Default")
      (node (ref "R15") (pin "1") (pinfunction "1_1") (pintype "passive"))
      (node (ref "U6") (pin "4") (pinfunction "EN_4") (pintype "passive"))
    )
    (net (code "155") (name "Net-(U8-EN)") (class "Default")
      (node (ref "R26") (pin "1") (pinfunction "1_1") (pintype "passive"))
      (node (ref "U8") (pin "4") (pinfunction "EN_4") (pintype "passive"))
    )
    (net (code "156") (name "VCC_3V3") (class "Default")
      (node (ref "C10") (pin "2") (pinfunction "2_2") (pintype "passive"))
      (node (ref "C11") (pin "2") (pinfunction "2_2") (pintype "passive"))
      (node (ref "C12") (pin "2") (pinfunction "2_2") (pintype "passive"))
      (node (ref "C13") (pin "1") (pinfunction "1_1") (pintype "passive"))
      (node (ref "C14") (pin "1") (pinfunction "1_1") (pintype "passive"))
      (node (ref "C15") (pin "1") (pinfunction "1_1") (pintype "passive"))
      (node (ref "C16") (pin "1") (pinfunction "1_1") (pintype "passive"))
      (node (ref "C17") (pin "1") (pinfunction "1_1") (pintype "passive"))
      (node (ref "C18") (pin "1") (pinfunction "1_1") (pintype "passive"))
      (node (ref "C19") (pin "1") (pinfunction "1_1") (pintype "passive"))
      (node (ref "C20") (pin "1") (pinfunction "1_1") (pintype "passive"))
      (node (ref "C21") (pin "1") (pinfunction "1_1") (pintype "passive"))
      (node (ref "C22") (pin "1") (pinfunction "1_1") (pintype "passive"))
      (node (ref "C23") (pin "1") (pinfunction "1_1") (pintype "passive"))
      (node (ref "C24") (pin "1") (pinfunction "1_1") (pintype "passive"))
      (node (ref "C25") (pin "1") (pinfunction "1_1") (pintype "passive"))
      (node (ref "C26") (pin "1") (pinfunction "1_1") (pintype "passive"))
      (node (ref "C27") (pin "1") (pinfunction "1_1") (pintype "passive"))
      (node (ref "C28") (pin "2") (pinfunction "2_2") (pintype "passive"))
      (node (ref "C29") (pin "2") (pinfunction "2_2") (pintype "passive"))
      (node (ref "C35") (pin "2") (pinfunction "2_2") (pintype "passive"))
      (node (ref "C49") (pin "2") (pinfunction "2_2") (pintype "passive"))
      (node (ref "C50") (pin "2") (pinfunction "2_2") (pintype "passive"))
      (node (ref "C53") (pin "1") (pinfunction "1_1") (pintype "passive"))
      (node (ref "C54") (pin "1") (pinfunction "1_1") (pintype "passive"))
      (node (ref "C56") (pin "1") (pinfunction "+_1") (pintype "passive"))
      (node (ref "C58") (pin "2") (pinfunction "2_2") (pintype "passive"))
      (node (ref "C7") (pin "2") (pinfunction "2_2") (pintype "passive"))
      (node (ref "C9") (pin "2") (pinfunction "2_2") (pintype "passive"))
      (node (ref "J1") (pin "6") (pinfunction "VCC_6") (pintype "passive"))
      (node (ref "J2") (pin "7") (pinfunction "DVDD_7") (pintype "passive"))
      (node (ref "L1") (pin "2") (pinfunction "2_2") (pintype "passive"))
      (node (ref "P2") (pin "4") (pinfunction "4_4") (pintype "passive"))
      (node (ref "P5") (pin "1") (pinfunction "1_1") (pintype "passive"))
      (node (ref "R1") (pin "2") (pinfunction "2_2") (pintype "passive"))
      (node (ref "R12") (pin "2") (pinfunction "2_2") (pintype "passive"))
      (node (ref "R17") (pin "2") (pinfunction "2_2") (pintype "passive"))
      (node (ref "R19") (pin "2") (pinfunction "2_2") (pintype "passive"))
      (node (ref "R20") (pin "2") (pinfunction "2_2") (pintype "passive"))
      (node (ref "R22") (pin "2") (pinfunction "2_2") (pintype "passive"))
      (node (ref "R24") (pin "2") (pinfunction "2_2") (pintype "passive"))
      (node (ref "R29") (pin "2") (pinfunction "2_2") (pintype "passive"))
      (node (ref "R30") (pin "2") (pinfunction "2_2") (pintype "passive"))
      (node (ref "R31") (pin "2") (pinfunction "2_2") (pintype "passive"))
      (node (ref "R32") (pin "2") (pinfunction "2_2") (pintype "passive"))
      (node (ref "R33") (pin "2") (pinfunction "2_2") (pintype "passive"))
      (node (ref "R4") (pin "1") (pinfunction "1_1") (pintype "passive"))
      (node (ref "R5") (pin "1") (pinfunction "1_1") (pintype "passive"))
      (node (ref "R9") (pin "1") (pinfunction "1_1") (pintype "passive"))
      (node (ref "TF1") (pin "4") (pinfunction "VDD_4") (pintype "passive"))
      (node (ref "U1") (pin "103") (pinfunction "VDD_103") (pintype "passive"))
      (node (ref "U1") (pin "114") (pinfunction "VDD_114") (pintype "passive"))
      (node (ref "U1") (pin "127") (pinfunction "VDD_127") (pintype "passive"))
      (node (ref "U1") (pin "136") (pinfunction "VDD_136") (pintype "passive"))
      (node (ref "U1") (pin "149") (pinfunction "VDD_149") (pintype "passive"))
      (node (ref "U1") (pin "15") (pinfunction "VDD_15") (pintype "passive"))
      (node (ref "U1") (pin "159") (pinfunction "VDD_159") (pintype "passive"))
      (node (ref "U1") (pin "171") (pinfunction "PDR_ON_171") (pintype "passive"))
      (node (ref "U1") (pin "172") (pinfunction "VDD_172") (pintype "passive"))
      (node (ref "U1") (pin "23") (pinfunction "VDD_23") (pintype "passive"))
      (node (ref "U1") (pin "36") (pinfunction "VDD_36") (pintype "passive"))
      (node (ref "U1") (pin "49") (pinfunction "VDD_49") (pintype "passive"))
      (node (ref "U1") (pin "6") (pinfunction "VBAT_6") (pintype "passive"))
      (node (ref "U1") (pin "62") (pinfunction "VDD_62") (pintype "passive"))
      (node (ref "U1") (pin "72") (pinfunction "VDD_72") (pintype "passive"))
      (node (ref "U1") (pin "82") (pinfunction "VDD_82") (pintype "passive"))
      (node (ref "U1") (pin "91") (pinfunction "VDD_91") (pintype "passive"))
      (node (ref "U2") (pin "1") (pinfunction "VDD_1") (pintype "passive"))
      (node (ref "U2") (pin "14") (pinfunction "VDD_14") (pintype "passive"))
      (node (ref "U2") (pin "27") (pinfunction "VDD_27") (pintype "passive"))
      (node (ref "U2") (pin "3") (pinfunction "VDDQ_3") (pintype "passive"))
      (node (ref "U2") (pin "43") (pinfunction "VDDQ_43") (pintype "passive"))
      (node (ref "U2") (pin "49") (pinfunction "VDDQ_49") (pintype "passive"))
      (node (ref "U2") (pin "9") (pinfunction "VDDQ_9") (pintype "passive"))
      (node (ref "U3") (pin "3") (pinfunction "W~{P}_3") (pintype "passive"))
      (node (ref "U3") (pin "7") (pinfunction "HOL~{D}_7") (pintype "passive"))
      (node (ref "U3") (pin "8") (pinfunction "VCC_8") (pintype "passive"))
      (node (ref "U7") (pin "2") (pinfunction "OUT_2") (pintype "passive"))
      (node (ref "U7") (pin "4") (pinfunction "OUT_4") (pintype "passive"))
    )
    (net (code "157") (name "VCC_5V") (class "Default")
      (node (ref "C44") (pin "2") (pinfunction "2_2") (pintype "passive"))
      (node (ref "C45") (pin "2") (pinfunction "2_2") (pintype "passive"))
      (node (ref "C51") (pin "2") (pinfunction "2_2") (pintype "passive"))
      (node (ref "C55") (pin "1") (pinfunction "+_1") (pintype "passive"))
      (node (ref "C57") (pin "2") (pinfunction "2_2") (pintype "passive"))
      (node (ref "L2") (pin "1") (pinfunction "1_1") (pintype "passive"))
      (node (ref "L3") (pin "1") (pinfunction "1_1") (pintype "passive"))
      (node (ref "P1") (pin "1") (pinfunction "1_1") (pintype "passive"))
      (node (ref "P1") (pin "2") (pinfunction "2_2") (pintype "passive"))
      (node (ref "P3") (pin "1") (pinfunction "1_1") (pintype "passive"))
      (node (ref "R15") (pin "2") (pinfunction "2_2") (pintype "passive"))
      (node (ref "U6") (pin "5") (pinfunction "IN_5") (pintype "passive"))
      (node (ref "U7") (pin "3") (pinfunction "IN_3") (pintype "passive"))
      (node (ref "U8") (pin "5") (pinfunction "IN_5") (pintype "passive"))
    )
    (net (code "158") (name "unconnected-(J2-NC-Pad45)") (class "Default")
      (node (ref "J2") (pin "45") (pinfunction "NC_45") (pintype "passive+no_connect"))
    )
    (net (code "159") (name "unconnected-(J2-NC-Pad49)") (class "Default")
      (node (ref "J2") (pin "49") (pinfunction "NC_49") (pintype "passive+no_connect"))
    )
    (net (code "160") (name "unconnected-(J2-NC-Pad50)") (class "Default")
      (node (ref "J2") (pin "50") (pinfunction "NC_50") (pintype "passive+no_connect"))
    )
    (net (code "161") (name "unconnected-(TF1-Pad9)") (class "Default")
      (node (ref "TF1") (pin "9") (pintype "passive+no_connect"))
    )
    (net (code "162") (name "unconnected-(TF1-Pad10)") (class "Default")
      (node (ref "TF1") (pin "10") (pintype "passive+no_connect"))
    )
    (net (code "163") (name "unconnected-(U1A-PA15-Pad138)") (class "Default")
      (node (ref "U1") (pin "138") (pinfunction "PA15_138") (pintype "passive+no_connect"))
    )
    (net (code "164") (name "unconnected-(U1A-PB3-Pad161)") (class "Default")
      (node (ref "U1") (pin "161") (pinfunction "PB3_161") (pintype "passive+no_connect"))
    )
    (net (code "165") (name "unconnected-(U1A-PB4-Pad162)") (class "Default")
      (node (ref "U1") (pin "162") (pinfunction "PB4_162") (pintype "passive+no_connect"))
    )
    (net (code "166") (name "unconnected-(U1A-PC14-Pad9)") (class "Default")
      (node (ref "U1") (pin "9") (pinfunction "PC14_9") (pintype "passive+no_connect"))
    )
    (net (code "167") (name "unconnected-(U1A-PC15-Pad10)") (class "Default")
      (node (ref "U1") (pin "10") (pinfunction "PC15_10") (pintype "passive+no_connect"))
    )
    (net (code "168") (name "unconnected-(U1B-PA2-Pad42)") (class "Default")
      (node (ref "U1") (pin "42") (pinfunction "PA2_42") (pintype "passive+no_connect"))
    )
    (net (code "169") (name "unconnected-(U1B-PA8-Pad119)") (class "Default")
      (node (ref "U1") (pin "119") (pinfunction "PA8_119") (pintype "passive+no_connect"))
    )
    (net (code "170") (name "unconnected-(U1B-PB5-Pad163)") (class "Default")
      (node (ref "U1") (pin "163") (pinfunction "PB5_163") (pintype "passive+no_connect"))
    )
    (net (code "171") (name "unconnected-(U1B-PB6-Pad164)") (class "Default")
      (node (ref "U1") (pin "164") (pinfunction "PB6_164") (pintype "passive+no_connect"))
    )
    (net (code "172") (name "unconnected-(U1B-PB7-Pad165)") (class "Default")
      (node (ref "U1") (pin "165") (pinfunction "PB7_165") (pintype "passive+no_connect"))
    )
    (net (code "173") (name "unconnected-(U1B-PC1-Pad33)") (class "Default")
      (node (ref "U1") (pin "33") (pinfunction "PC1_33") (pintype "passive+no_connect"))
    )
    (net (code "174") (name "unconnected-(U1B-PC2-Pad34)") (class "Default")
      (node (ref "U1") (pin "34") (pinfunction "PC2_34") (pintype "passive+no_connect"))
    )
    (net (code "175") (name "unconnected-(U1B-PC3-Pad35)") (class "Default")
      (node (ref "U1") (pin "35") (pinfunction "PC3_35") (pintype "passive+no_connect"))
    )
    (net (code "176") (name "unconnected-(U1B-PC5-Pad55)") (class "Default")
      (node (ref "U1") (pin "55") (pinfunction "PC5_55") (pintype "passive+no_connect"))
    )
    (net (code "177") (name "unconnected-(U1B-PC6-Pad115)") (class "Default")
      (node (ref "U1") (pin "115") (pinfunction "PC6_115") (pintype "passive+no_connect"))
    )
    (net (code "178") (name "unconnected-(U1B-PC13-Pad8)") (class "Default")
      (node (ref "U1") (pin "8") (pinfunction "PC13_8") (pintype "passive+no_connect"))
    )
    (net (code "179") (name "unconnected-(U1B-PD3-Pad145)") (class "Default")
      (node (ref "U1") (pin "145") (pinfunction "PD3_145") (pintype "passive+no_connect"))
    )
    (net (code "180") (name "unconnected-(U1B-PD4-Pad146)") (class "Default")
      (node (ref "U1") (pin "146") (pinfunction "PD4_146") (pintype "passive+no_connect"))
    )
    (net (code "181") (name "unconnected-(U1B-PD5-Pad147)") (class "Default")
      (node (ref "U1") (pin "147") (pinfunction "PD5_147") (pintype "passive+no_connect"))
    )
    (net (code "182") (name "unconnected-(U1B-PD12-Pad100)") (class "Default")
      (node (ref "U1") (pin "100") (pinfunction "PD12_100") (pintype "passive+no_connect"))
    )
    (net (code "183") (name "unconnected-(U1B-PE2-Pad1)") (class "Default")
      (node (ref "U1") (pin "1") (pinfunction "PE2_1") (pintype "passive+no_connect"))
    )
    (net (code "184") (name "unconnected-(U1B-PE3-Pad2)") (class "Default")
      (node (ref "U1") (pin "2") (pinfunction "PE3_2") (pintype "passive+no_connect"))
    )
    (net (code "185") (name "unconnected-(U1B-PG2-Pad106)") (class "Default")
      (node (ref "U1") (pin "106") (pinfunction "PG2_106") (pintype "passive+no_connect"))
    )
    (net (code "186") (name "unconnected-(U1B-PG3-Pad107)") (class "Default")
      (node (ref "U1") (pin "107") (pinfunction "PG3_107") (pintype "passive+no_connect"))
    )
    (net (code "187") (name "unconnected-(U1B-PG9-Pad152)") (class "Default")
      (node (ref "U1") (pin "152") (pinfunction "PG9_152") (pintype "passive+no_connect"))
    )
    (net (code "188") (name "unconnected-(U1B-PG13-Pad156)") (class "Default")
      (node (ref "U1") (pin "156") (pinfunction "PG13_156") (pintype "passive+no_connect"))
    )
    (net (code "189") (name "unconnected-(U1B-PG14-Pad157)") (class "Default")
      (node (ref "U1") (pin "157") (pinfunction "PG14_157") (pintype "passive+no_connect"))
    )
    (net (code "190") (name "unconnected-(U1B-PH9-Pad86)") (class "Default")
      (node (ref "U1") (pin "86") (pinfunction "PH9_86") (pintype "passive+no_connect"))
    )
    (net (code "191") (name "unconnected-(U1B-PH10-Pad87)") (class "Default")
      (node (ref "U1") (pin "87") (pinfunction "PH10_87") (pintype "passive+no_connect"))
    )
    (net (code "192") (name "unconnected-(U1B-PH11-Pad88)") (class "Default")
      (node (ref "U1") (pin "88") (pinfunction "PH11_88") (pintype "passive+no_connect"))
    )
    (net (code "193") (name "unconnected-(U1B-PH12-Pad89)") (class "Default")
      (node (ref "U1") (pin "89") (pinfunction "PH12_89") (pintype "passive+no_connect"))
    )
    (net (code "194") (name "unconnected-(U1B-PH14-Pad129)") (class "Default")
      (node (ref "U1") (pin "129") (pinfunction "PH14_129") (pintype "passive"))
    )
    (net (code "195") (name "unconnected-(U1B-PI1-Pad132)") (class "Default")
      (node (ref "U1") (pin "132") (pinfunction "PI1_132") (pintype "passive+no_connect"))
    )
    (net (code "196") (name "unconnected-(U1B-PI3-Pad134)") (class "Default")
      (node (ref "U1") (pin "134") (pinfunction "PI3_134") (pintype "passive+no_connect"))
    )
    (net (code "197") (name "unconnected-(U1B-PI5-Pad174)") (class "Default")
      (node (ref "U1") (pin "174") (pinfunction "PI5_174") (pintype "passive+no_connect"))
    )
    (net (code "198") (name "unconnected-(U1B-PI6-Pad175)") (class "Default")
      (node (ref "U1") (pin "175") (pinfunction "PI6_175") (pintype "passive+no_connect"))
    )
    (net (code "199") (name "unconnected-(U1B-PI7-Pad176)") (class "Default")
      (node (ref "U1") (pin "176") (pinfunction "PI7_176") (pintype "passive+no_connect"))
    )
    (net (code "200") (name "unconnected-(U1B-PI8-Pad7)") (class "Default")
      (node (ref "U1") (pin "7") (pinfunction "PI8_7") (pintype "passive+no_connect"))
    )
    (net (code "201") (name "unconnected-(U1B-PI11-Pad13)") (class "Default")
      (node (ref "U1") (pin "13") (pinfunction "PI11_13") (pintype "passive+no_connect"))
    )
    (net (code "202") (name "unconnected-(U2-NC-Pad36)") (class "Default")
      (node (ref "U2") (pin "36") (pinfunction "NC_36") (pintype "passive+no_connect"))
    )
    (net (code "203") (name "unconnected-(U2-NC-Pad40)") (class "Default")
      (node (ref "U2") (pin "40") (pinfunction "NC_40") (pintype "passive+no_connect"))
    )
  )
)
